# GR740_Memory.net
KiCad netlist of a schematic drawn in Altium Designer
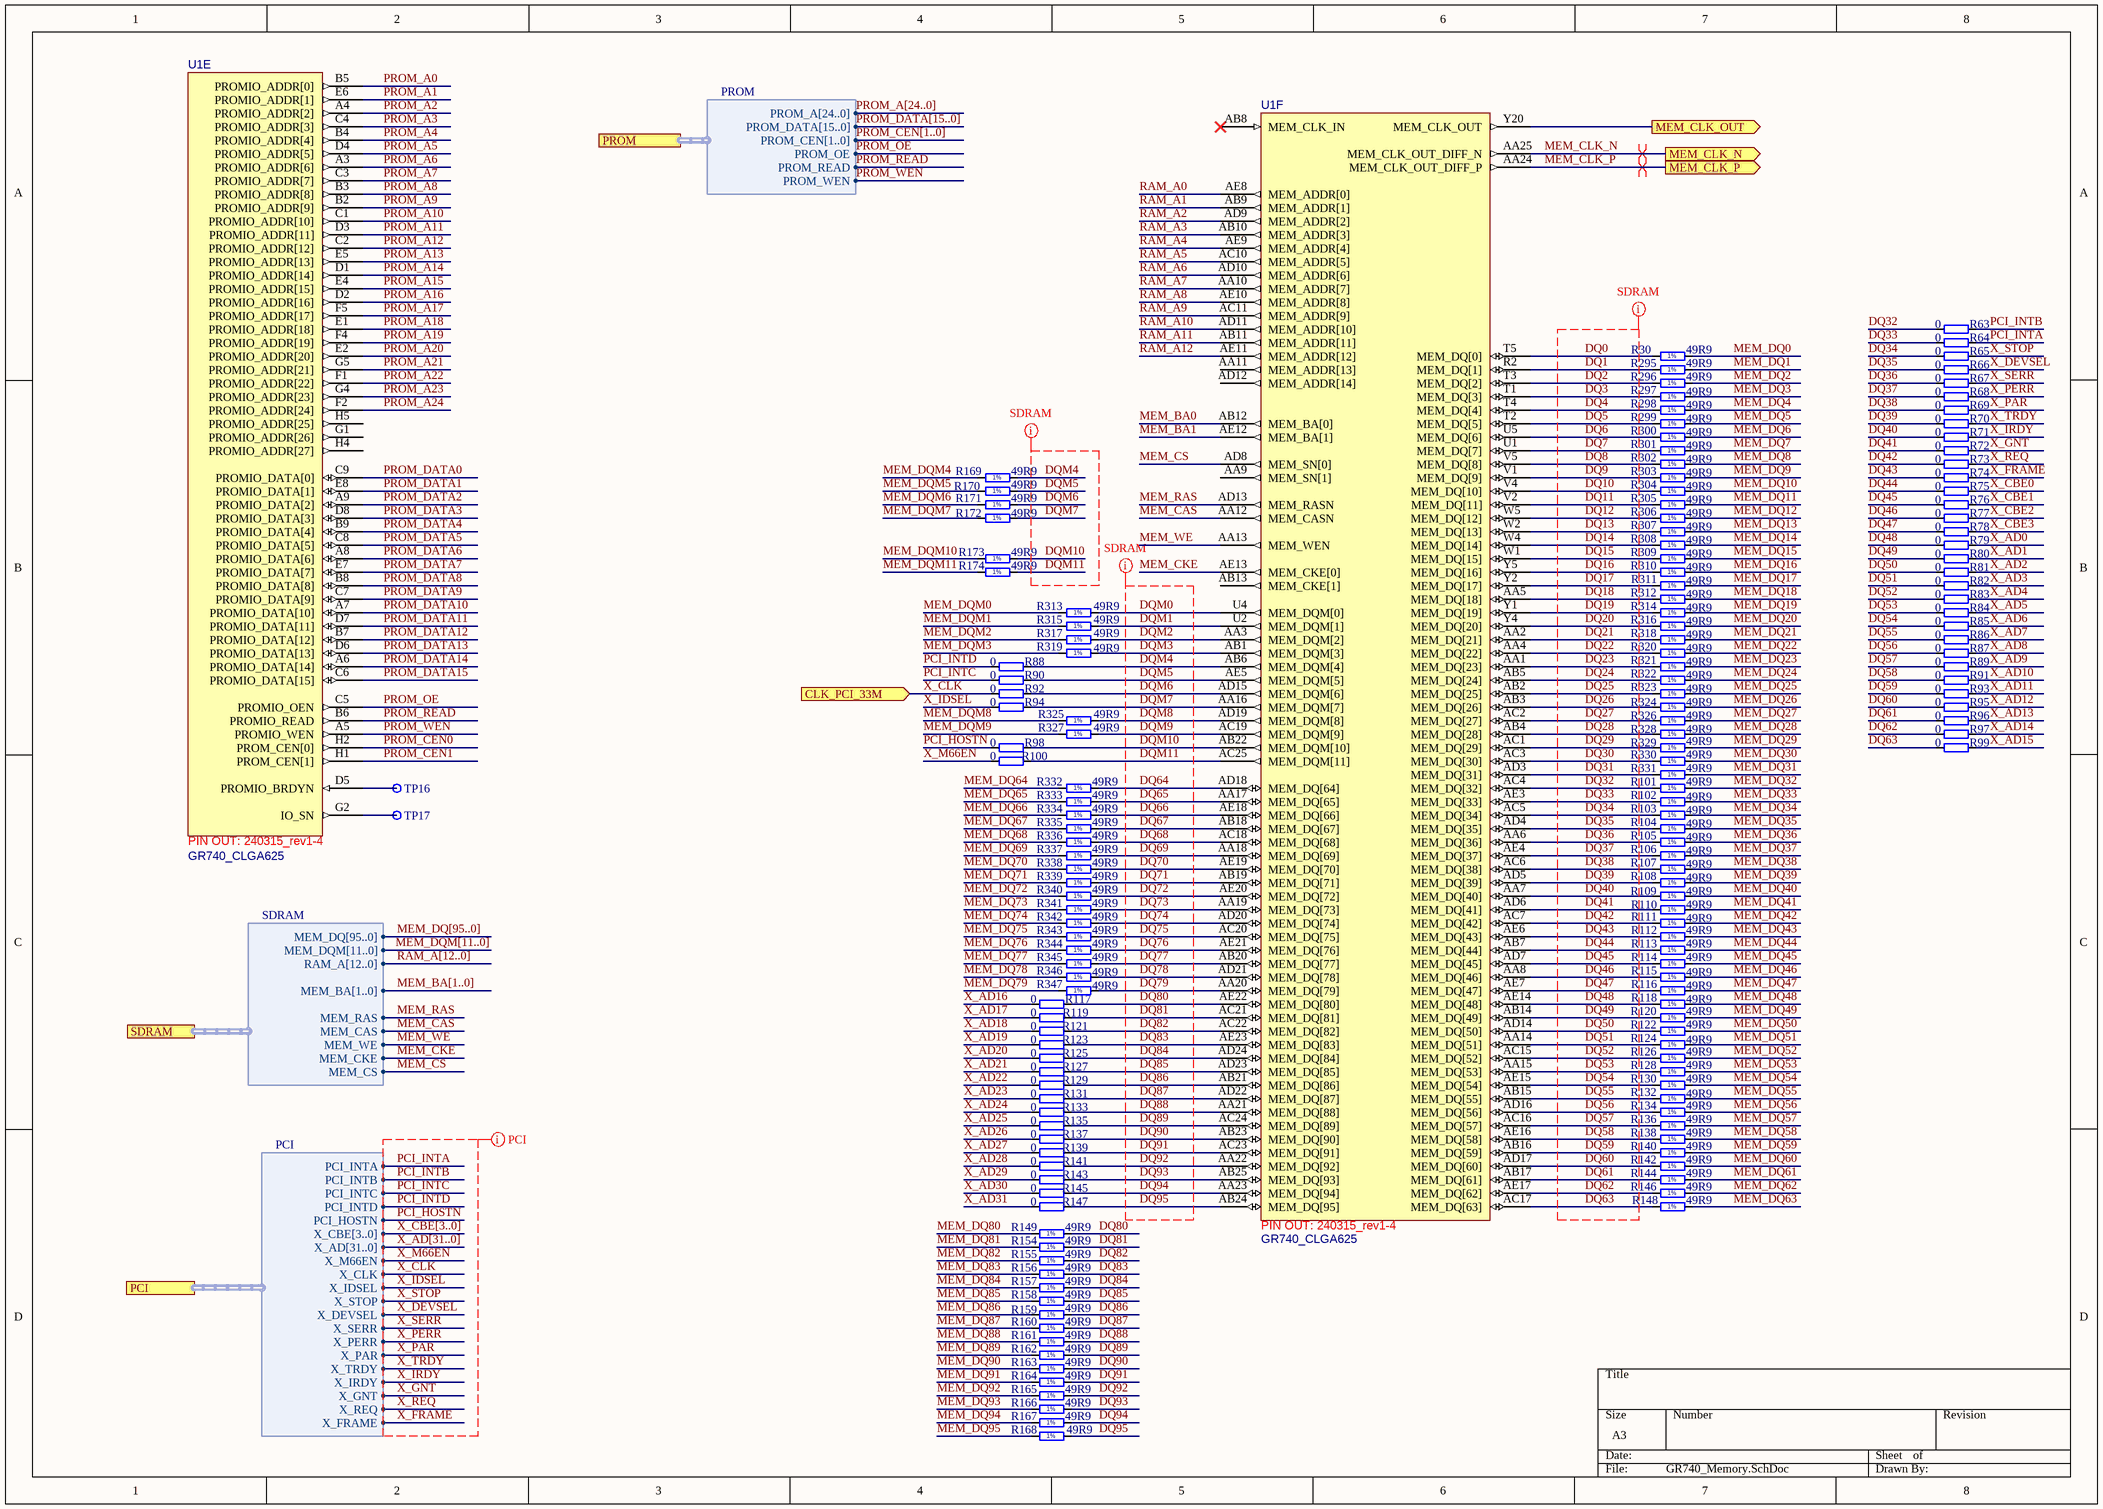
[diagram p0: GR740_Memory.SchDoc]

(export (version "E")
  (design (tool "Eeschema 10.0.6"))
  (components
    (comp (ref "R30")
      (value "49R9")
      (footprint "RESC0603X28N")
      (description "Resistor - 1%")
      (fields
        (field (name "PART NUMBER") "R0201_49R9_1%_0.05W_200PPM")
        (field (name "MANUFACTURER") "GENERIC")
        (field (name "AUTHOR") "CERN DEM BC")
      )
      (libsource (lib "Resistors") (part "Resistor - 1%"))
    )
    (comp (ref "R63")
      (value "0")
      (footprint "RESC0603X28N")
      (description "Resistor")
      (fields
        (field (name "PART NUMBER") "R0201_0R_JUMPER")
        (field (name "MANUFACTURER") "GENERIC")
        (field (name "AUTHOR") "CERN DEM JLC")
      )
      (libsource (lib "Resistors") (part "Resistor"))
    )
    (comp (ref "R64")
      (value "0")
      (footprint "RESC0603X28N")
      (description "Resistor")
      (fields
        (field (name "PART NUMBER") "R0201_0R_JUMPER")
        (field (name "MANUFACTURER") "GENERIC")
        (field (name "AUTHOR") "CERN DEM JLC")
      )
      (libsource (lib "Resistors") (part "Resistor"))
    )
    (comp (ref "R65")
      (value "0")
      (footprint "RESC0603X28N")
      (description "Resistor")
      (fields
        (field (name "PART NUMBER") "R0201_0R_JUMPER")
        (field (name "MANUFACTURER") "GENERIC")
        (field (name "AUTHOR") "CERN DEM JLC")
      )
      (libsource (lib "Resistors") (part "Resistor"))
    )
    (comp (ref "R66")
      (value "0")
      (footprint "RESC0603X28N")
      (description "Resistor")
      (fields
        (field (name "PART NUMBER") "R0201_0R_JUMPER")
        (field (name "MANUFACTURER") "GENERIC")
        (field (name "AUTHOR") "CERN DEM JLC")
      )
      (libsource (lib "Resistors") (part "Resistor"))
    )
    (comp (ref "R67")
      (value "0")
      (footprint "RESC0603X28N")
      (description "Resistor")
      (fields
        (field (name "PART NUMBER") "R0201_0R_JUMPER")
        (field (name "MANUFACTURER") "GENERIC")
        (field (name "AUTHOR") "CERN DEM JLC")
      )
      (libsource (lib "Resistors") (part "Resistor"))
    )
    (comp (ref "R68")
      (value "0")
      (footprint "RESC0603X28N")
      (description "Resistor")
      (fields
        (field (name "PART NUMBER") "R0201_0R_JUMPER")
        (field (name "MANUFACTURER") "GENERIC")
        (field (name "AUTHOR") "CERN DEM JLC")
      )
      (libsource (lib "Resistors") (part "Resistor"))
    )
    (comp (ref "R69")
      (value "0")
      (footprint "RESC0603X28N")
      (description "Resistor")
      (fields
        (field (name "PART NUMBER") "R0201_0R_JUMPER")
        (field (name "MANUFACTURER") "GENERIC")
        (field (name "AUTHOR") "CERN DEM JLC")
      )
      (libsource (lib "Resistors") (part "Resistor"))
    )
    (comp (ref "R70")
      (value "0")
      (footprint "RESC0603X28N")
      (description "Resistor")
      (fields
        (field (name "PART NUMBER") "R0201_0R_JUMPER")
        (field (name "MANUFACTURER") "GENERIC")
        (field (name "AUTHOR") "CERN DEM JLC")
      )
      (libsource (lib "Resistors") (part "Resistor"))
    )
    (comp (ref "R71")
      (value "0")
      (footprint "RESC0603X28N")
      (description "Resistor")
      (fields
        (field (name "PART NUMBER") "R0201_0R_JUMPER")
        (field (name "MANUFACTURER") "GENERIC")
        (field (name "AUTHOR") "CERN DEM JLC")
      )
      (libsource (lib "Resistors") (part "Resistor"))
    )
    (comp (ref "R72")
      (value "0")
      (footprint "RESC0603X28N")
      (description "Resistor")
      (fields
        (field (name "PART NUMBER") "R0201_0R_JUMPER")
        (field (name "MANUFACTURER") "GENERIC")
        (field (name "AUTHOR") "CERN DEM JLC")
      )
      (libsource (lib "Resistors") (part "Resistor"))
    )
    (comp (ref "R73")
      (value "0")
      (footprint "RESC0603X28N")
      (description "Resistor")
      (fields
        (field (name "PART NUMBER") "R0201_0R_JUMPER")
        (field (name "MANUFACTURER") "GENERIC")
        (field (name "AUTHOR") "CERN DEM JLC")
      )
      (libsource (lib "Resistors") (part "Resistor"))
    )
    (comp (ref "R74")
      (value "0")
      (footprint "RESC0603X28N")
      (description "Resistor")
      (fields
        (field (name "PART NUMBER") "R0201_0R_JUMPER")
        (field (name "MANUFACTURER") "GENERIC")
        (field (name "AUTHOR") "CERN DEM JLC")
      )
      (libsource (lib "Resistors") (part "Resistor"))
    )
    (comp (ref "R75")
      (value "0")
      (footprint "RESC0603X28N")
      (description "Resistor")
      (fields
        (field (name "PART NUMBER") "R0201_0R_JUMPER")
        (field (name "MANUFACTURER") "GENERIC")
        (field (name "AUTHOR") "CERN DEM JLC")
      )
      (libsource (lib "Resistors") (part "Resistor"))
    )
    (comp (ref "R76")
      (value "0")
      (footprint "RESC0603X28N")
      (description "Resistor")
      (fields
        (field (name "PART NUMBER") "R0201_0R_JUMPER")
        (field (name "MANUFACTURER") "GENERIC")
        (field (name "AUTHOR") "CERN DEM JLC")
      )
      (libsource (lib "Resistors") (part "Resistor"))
    )
    (comp (ref "R77")
      (value "0")
      (footprint "RESC0603X28N")
      (description "Resistor")
      (fields
        (field (name "PART NUMBER") "R0201_0R_JUMPER")
        (field (name "MANUFACTURER") "GENERIC")
        (field (name "AUTHOR") "CERN DEM JLC")
      )
      (libsource (lib "Resistors") (part "Resistor"))
    )
    (comp (ref "R78")
      (value "0")
      (footprint "RESC0603X28N")
      (description "Resistor")
      (fields
        (field (name "PART NUMBER") "R0201_0R_JUMPER")
        (field (name "MANUFACTURER") "GENERIC")
        (field (name "AUTHOR") "CERN DEM JLC")
      )
      (libsource (lib "Resistors") (part "Resistor"))
    )
    (comp (ref "R79")
      (value "0")
      (footprint "RESC0603X28N")
      (description "Resistor")
      (fields
        (field (name "PART NUMBER") "R0201_0R_JUMPER")
        (field (name "MANUFACTURER") "GENERIC")
        (field (name "AUTHOR") "CERN DEM JLC")
      )
      (libsource (lib "Resistors") (part "Resistor"))
    )
    (comp (ref "R80")
      (value "0")
      (footprint "RESC0603X28N")
      (description "Resistor")
      (fields
        (field (name "PART NUMBER") "R0201_0R_JUMPER")
        (field (name "MANUFACTURER") "GENERIC")
        (field (name "AUTHOR") "CERN DEM JLC")
      )
      (libsource (lib "Resistors") (part "Resistor"))
    )
    (comp (ref "R81")
      (value "0")
      (footprint "RESC0603X28N")
      (description "Resistor")
      (fields
        (field (name "PART NUMBER") "R0201_0R_JUMPER")
        (field (name "MANUFACTURER") "GENERIC")
        (field (name "AUTHOR") "CERN DEM JLC")
      )
      (libsource (lib "Resistors") (part "Resistor"))
    )
    (comp (ref "R82")
      (value "0")
      (footprint "RESC0603X28N")
      (description "Resistor")
      (fields
        (field (name "PART NUMBER") "R0201_0R_JUMPER")
        (field (name "MANUFACTURER") "GENERIC")
        (field (name "AUTHOR") "CERN DEM JLC")
      )
      (libsource (lib "Resistors") (part "Resistor"))
    )
    (comp (ref "R83")
      (value "0")
      (footprint "RESC0603X28N")
      (description "Resistor")
      (fields
        (field (name "PART NUMBER") "R0201_0R_JUMPER")
        (field (name "MANUFACTURER") "GENERIC")
        (field (name "AUTHOR") "CERN DEM JLC")
      )
      (libsource (lib "Resistors") (part "Resistor"))
    )
    (comp (ref "R84")
      (value "0")
      (footprint "RESC0603X28N")
      (description "Resistor")
      (fields
        (field (name "PART NUMBER") "R0201_0R_JUMPER")
        (field (name "MANUFACTURER") "GENERIC")
        (field (name "AUTHOR") "CERN DEM JLC")
      )
      (libsource (lib "Resistors") (part "Resistor"))
    )
    (comp (ref "R85")
      (value "0")
      (footprint "RESC0603X28N")
      (description "Resistor")
      (fields
        (field (name "PART NUMBER") "R0201_0R_JUMPER")
        (field (name "MANUFACTURER") "GENERIC")
        (field (name "AUTHOR") "CERN DEM JLC")
      )
      (libsource (lib "Resistors") (part "Resistor"))
    )
    (comp (ref "R86")
      (value "0")
      (footprint "RESC0603X28N")
      (description "Resistor")
      (fields
        (field (name "PART NUMBER") "R0201_0R_JUMPER")
        (field (name "MANUFACTURER") "GENERIC")
        (field (name "AUTHOR") "CERN DEM JLC")
      )
      (libsource (lib "Resistors") (part "Resistor"))
    )
    (comp (ref "R87")
      (value "0")
      (footprint "RESC0603X28N")
      (description "Resistor")
      (fields
        (field (name "PART NUMBER") "R0201_0R_JUMPER")
        (field (name "MANUFACTURER") "GENERIC")
        (field (name "AUTHOR") "CERN DEM JLC")
      )
      (libsource (lib "Resistors") (part "Resistor"))
    )
    (comp (ref "R88")
      (value "0")
      (footprint "RESC0603X28N")
      (description "Resistor")
      (fields
        (field (name "PART NUMBER") "R0201_0R_JUMPER")
        (field (name "MANUFACTURER") "GENERIC")
        (field (name "AUTHOR") "CERN DEM JLC")
      )
      (libsource (lib "Resistors") (part "Resistor"))
    )
    (comp (ref "R89")
      (value "0")
      (footprint "RESC0603X28N")
      (description "Resistor")
      (fields
        (field (name "PART NUMBER") "R0201_0R_JUMPER")
        (field (name "MANUFACTURER") "GENERIC")
        (field (name "AUTHOR") "CERN DEM JLC")
      )
      (libsource (lib "Resistors") (part "Resistor"))
    )
    (comp (ref "R90")
      (value "0")
      (footprint "RESC0603X28N")
      (description "Resistor")
      (fields
        (field (name "PART NUMBER") "R0201_0R_JUMPER")
        (field (name "MANUFACTURER") "GENERIC")
        (field (name "AUTHOR") "CERN DEM JLC")
      )
      (libsource (lib "Resistors") (part "Resistor"))
    )
    (comp (ref "R91")
      (value "0")
      (footprint "RESC0603X28N")
      (description "Resistor")
      (fields
        (field (name "PART NUMBER") "R0201_0R_JUMPER")
        (field (name "MANUFACTURER") "GENERIC")
        (field (name "AUTHOR") "CERN DEM JLC")
      )
      (libsource (lib "Resistors") (part "Resistor"))
    )
    (comp (ref "R92")
      (value "0")
      (footprint "RESC0603X28N")
      (description "Resistor")
      (fields
        (field (name "PART NUMBER") "R0201_0R_JUMPER")
        (field (name "MANUFACTURER") "GENERIC")
        (field (name "AUTHOR") "CERN DEM JLC")
      )
      (libsource (lib "Resistors") (part "Resistor"))
    )
    (comp (ref "R93")
      (value "0")
      (footprint "RESC0603X28N")
      (description "Resistor")
      (fields
        (field (name "PART NUMBER") "R0201_0R_JUMPER")
        (field (name "MANUFACTURER") "GENERIC")
        (field (name "AUTHOR") "CERN DEM JLC")
      )
      (libsource (lib "Resistors") (part "Resistor"))
    )
    (comp (ref "R94")
      (value "0")
      (footprint "RESC0603X28N")
      (description "Resistor")
      (fields
        (field (name "PART NUMBER") "R0201_0R_JUMPER")
        (field (name "MANUFACTURER") "GENERIC")
        (field (name "AUTHOR") "CERN DEM JLC")
      )
      (libsource (lib "Resistors") (part "Resistor"))
    )
    (comp (ref "R95")
      (value "0")
      (footprint "RESC0603X28N")
      (description "Resistor")
      (fields
        (field (name "PART NUMBER") "R0201_0R_JUMPER")
        (field (name "MANUFACTURER") "GENERIC")
        (field (name "AUTHOR") "CERN DEM JLC")
      )
      (libsource (lib "Resistors") (part "Resistor"))
    )
    (comp (ref "R96")
      (value "0")
      (footprint "RESC0603X28N")
      (description "Resistor")
      (fields
        (field (name "PART NUMBER") "R0201_0R_JUMPER")
        (field (name "MANUFACTURER") "GENERIC")
        (field (name "AUTHOR") "CERN DEM JLC")
      )
      (libsource (lib "Resistors") (part "Resistor"))
    )
    (comp (ref "R97")
      (value "0")
      (footprint "RESC0603X28N")
      (description "Resistor")
      (fields
        (field (name "PART NUMBER") "R0201_0R_JUMPER")
        (field (name "MANUFACTURER") "GENERIC")
        (field (name "AUTHOR") "CERN DEM JLC")
      )
      (libsource (lib "Resistors") (part "Resistor"))
    )
    (comp (ref "R98")
      (value "0")
      (footprint "RESC0603X28N")
      (description "Resistor")
      (fields
        (field (name "PART NUMBER") "R0201_0R_JUMPER")
        (field (name "MANUFACTURER") "GENERIC")
        (field (name "AUTHOR") "CERN DEM JLC")
      )
      (libsource (lib "Resistors") (part "Resistor"))
    )
    (comp (ref "R99")
      (value "0")
      (footprint "RESC0603X28N")
      (description "Resistor")
      (fields
        (field (name "PART NUMBER") "R0201_0R_JUMPER")
        (field (name "MANUFACTURER") "GENERIC")
        (field (name "AUTHOR") "CERN DEM JLC")
      )
      (libsource (lib "Resistors") (part "Resistor"))
    )
    (comp (ref "R100")
      (value "0")
      (footprint "RESC0603X28N")
      (description "Resistor")
      (fields
        (field (name "PART NUMBER") "R0201_0R_JUMPER")
        (field (name "MANUFACTURER") "GENERIC")
        (field (name "AUTHOR") "CERN DEM JLC")
      )
      (libsource (lib "Resistors") (part "Resistor"))
    )
    (comp (ref "R101")
      (value "49R9")
      (footprint "RESC0603X28N")
      (description "Resistor - 1%")
      (fields
        (field (name "PART NUMBER") "R0201_49R9_1%_0.05W_200PPM")
        (field (name "MANUFACTURER") "GENERIC")
        (field (name "AUTHOR") "CERN DEM BC")
      )
      (libsource (lib "Resistors") (part "Resistor - 1%"))
    )
    (comp (ref "R102")
      (value "49R9")
      (footprint "RESC0603X28N")
      (description "Resistor - 1%")
      (fields
        (field (name "PART NUMBER") "R0201_49R9_1%_0.05W_200PPM")
        (field (name "MANUFACTURER") "GENERIC")
        (field (name "AUTHOR") "CERN DEM BC")
      )
      (libsource (lib "Resistors") (part "Resistor - 1%"))
    )
    (comp (ref "R103")
      (value "49R9")
      (footprint "RESC0603X28N")
      (description "Resistor - 1%")
      (fields
        (field (name "PART NUMBER") "R0201_49R9_1%_0.05W_200PPM")
        (field (name "MANUFACTURER") "GENERIC")
        (field (name "AUTHOR") "CERN DEM BC")
      )
      (libsource (lib "Resistors") (part "Resistor - 1%"))
    )
    (comp (ref "R104")
      (value "49R9")
      (footprint "RESC0603X28N")
      (description "Resistor - 1%")
      (fields
        (field (name "PART NUMBER") "R0201_49R9_1%_0.05W_200PPM")
        (field (name "MANUFACTURER") "GENERIC")
        (field (name "AUTHOR") "CERN DEM BC")
      )
      (libsource (lib "Resistors") (part "Resistor - 1%"))
    )
    (comp (ref "R105")
      (value "49R9")
      (footprint "RESC0603X28N")
      (description "Resistor - 1%")
      (fields
        (field (name "PART NUMBER") "R0201_49R9_1%_0.05W_200PPM")
        (field (name "MANUFACTURER") "GENERIC")
        (field (name "AUTHOR") "CERN DEM BC")
      )
      (libsource (lib "Resistors") (part "Resistor - 1%"))
    )
    (comp (ref "R106")
      (value "49R9")
      (footprint "RESC0603X28N")
      (description "Resistor - 1%")
      (fields
        (field (name "PART NUMBER") "R0201_49R9_1%_0.05W_200PPM")
        (field (name "MANUFACTURER") "GENERIC")
        (field (name "AUTHOR") "CERN DEM BC")
      )
      (libsource (lib "Resistors") (part "Resistor - 1%"))
    )
    (comp (ref "R107")
      (value "49R9")
      (footprint "RESC0603X28N")
      (description "Resistor - 1%")
      (fields
        (field (name "PART NUMBER") "R0201_49R9_1%_0.05W_200PPM")
        (field (name "MANUFACTURER") "GENERIC")
        (field (name "AUTHOR") "CERN DEM BC")
      )
      (libsource (lib "Resistors") (part "Resistor - 1%"))
    )
    (comp (ref "R108")
      (value "49R9")
      (footprint "RESC0603X28N")
      (description "Resistor - 1%")
      (fields
        (field (name "PART NUMBER") "R0201_49R9_1%_0.05W_200PPM")
        (field (name "MANUFACTURER") "GENERIC")
        (field (name "AUTHOR") "CERN DEM BC")
      )
      (libsource (lib "Resistors") (part "Resistor - 1%"))
    )
    (comp (ref "R109")
      (value "49R9")
      (footprint "RESC0603X28N")
      (description "Resistor - 1%")
      (fields
        (field (name "PART NUMBER") "R0201_49R9_1%_0.05W_200PPM")
        (field (name "MANUFACTURER") "GENERIC")
        (field (name "AUTHOR") "CERN DEM BC")
      )
      (libsource (lib "Resistors") (part "Resistor - 1%"))
    )
    (comp (ref "R110")
      (value "49R9")
      (footprint "RESC0603X28N")
      (description "Resistor - 1%")
      (fields
        (field (name "PART NUMBER") "R0201_49R9_1%_0.05W_200PPM")
        (field (name "MANUFACTURER") "GENERIC")
        (field (name "AUTHOR") "CERN DEM BC")
      )
      (libsource (lib "Resistors") (part "Resistor - 1%"))
    )
    (comp (ref "R111")
      (value "49R9")
      (footprint "RESC0603X28N")
      (description "Resistor - 1%")
      (fields
        (field (name "PART NUMBER") "R0201_49R9_1%_0.05W_200PPM")
        (field (name "MANUFACTURER") "GENERIC")
        (field (name "AUTHOR") "CERN DEM BC")
      )
      (libsource (lib "Resistors") (part "Resistor - 1%"))
    )
    (comp (ref "R112")
      (value "49R9")
      (footprint "RESC0603X28N")
      (description "Resistor - 1%")
      (fields
        (field (name "PART NUMBER") "R0201_49R9_1%_0.05W_200PPM")
        (field (name "MANUFACTURER") "GENERIC")
        (field (name "AUTHOR") "CERN DEM BC")
      )
      (libsource (lib "Resistors") (part "Resistor - 1%"))
    )
    (comp (ref "R113")
      (value "49R9")
      (footprint "RESC0603X28N")
      (description "Resistor - 1%")
      (fields
        (field (name "PART NUMBER") "R0201_49R9_1%_0.05W_200PPM")
        (field (name "MANUFACTURER") "GENERIC")
        (field (name "AUTHOR") "CERN DEM BC")
      )
      (libsource (lib "Resistors") (part "Resistor - 1%"))
    )
    (comp (ref "R114")
      (value "49R9")
      (footprint "RESC0603X28N")
      (description "Resistor - 1%")
      (fields
        (field (name "PART NUMBER") "R0201_49R9_1%_0.05W_200PPM")
        (field (name "MANUFACTURER") "GENERIC")
        (field (name "AUTHOR") "CERN DEM BC")
      )
      (libsource (lib "Resistors") (part "Resistor - 1%"))
    )
    (comp (ref "R115")
      (value "49R9")
      (footprint "RESC0603X28N")
      (description "Resistor - 1%")
      (fields
        (field (name "PART NUMBER") "R0201_49R9_1%_0.05W_200PPM")
        (field (name "MANUFACTURER") "GENERIC")
        (field (name "AUTHOR") "CERN DEM BC")
      )
      (libsource (lib "Resistors") (part "Resistor - 1%"))
    )
    (comp (ref "R116")
      (value "49R9")
      (footprint "RESC0603X28N")
      (description "Resistor - 1%")
      (fields
        (field (name "PART NUMBER") "R0201_49R9_1%_0.05W_200PPM")
        (field (name "MANUFACTURER") "GENERIC")
        (field (name "AUTHOR") "CERN DEM BC")
      )
      (libsource (lib "Resistors") (part "Resistor - 1%"))
    )
    (comp (ref "R117")
      (value "0")
      (footprint "RESC0603X28N")
      (description "Resistor")
      (fields
        (field (name "PART NUMBER") "R0201_0R_JUMPER")
        (field (name "MANUFACTURER") "GENERIC")
        (field (name "AUTHOR") "CERN DEM JLC")
      )
      (libsource (lib "Resistors") (part "Resistor"))
    )
    (comp (ref "R118")
      (value "49R9")
      (footprint "RESC0603X28N")
      (description "Resistor - 1%")
      (fields
        (field (name "PART NUMBER") "R0201_49R9_1%_0.05W_200PPM")
        (field (name "MANUFACTURER") "GENERIC")
        (field (name "AUTHOR") "CERN DEM BC")
      )
      (libsource (lib "Resistors") (part "Resistor - 1%"))
    )
    (comp (ref "R119")
      (value "0")
      (footprint "RESC0603X28N")
      (description "Resistor")
      (fields
        (field (name "PART NUMBER") "R0201_0R_JUMPER")
        (field (name "MANUFACTURER") "GENERIC")
        (field (name "AUTHOR") "CERN DEM JLC")
      )
      (libsource (lib "Resistors") (part "Resistor"))
    )
    (comp (ref "R120")
      (value "49R9")
      (footprint "RESC0603X28N")
      (description "Resistor - 1%")
      (fields
        (field (name "PART NUMBER") "R0201_49R9_1%_0.05W_200PPM")
        (field (name "MANUFACTURER") "GENERIC")
        (field (name "AUTHOR") "CERN DEM BC")
      )
      (libsource (lib "Resistors") (part "Resistor - 1%"))
    )
    (comp (ref "R121")
      (value "0")
      (footprint "RESC0603X28N")
      (description "Resistor")
      (fields
        (field (name "PART NUMBER") "R0201_0R_JUMPER")
        (field (name "MANUFACTURER") "GENERIC")
        (field (name "AUTHOR") "CERN DEM JLC")
      )
      (libsource (lib "Resistors") (part "Resistor"))
    )
    (comp (ref "R122")
      (value "49R9")
      (footprint "RESC0603X28N")
      (description "Resistor - 1%")
      (fields
        (field (name "PART NUMBER") "R0201_49R9_1%_0.05W_200PPM")
        (field (name "MANUFACTURER") "GENERIC")
        (field (name "AUTHOR") "CERN DEM BC")
      )
      (libsource (lib "Resistors") (part "Resistor - 1%"))
    )
    (comp (ref "R123")
      (value "0")
      (footprint "RESC0603X28N")
      (description "Resistor")
      (fields
        (field (name "PART NUMBER") "R0201_0R_JUMPER")
        (field (name "MANUFACTURER") "GENERIC")
        (field (name "AUTHOR") "CERN DEM JLC")
      )
      (libsource (lib "Resistors") (part "Resistor"))
    )
    (comp (ref "R124")
      (value "49R9")
      (footprint "RESC0603X28N")
      (description "Resistor - 1%")
      (fields
        (field (name "PART NUMBER") "R0201_49R9_1%_0.05W_200PPM")
        (field (name "MANUFACTURER") "GENERIC")
        (field (name "AUTHOR") "CERN DEM BC")
      )
      (libsource (lib "Resistors") (part "Resistor - 1%"))
    )
    (comp (ref "R125")
      (value "0")
      (footprint "RESC0603X28N")
      (description "Resistor")
      (fields
        (field (name "PART NUMBER") "R0201_0R_JUMPER")
        (field (name "MANUFACTURER") "GENERIC")
        (field (name "AUTHOR") "CERN DEM JLC")
      )
      (libsource (lib "Resistors") (part "Resistor"))
    )
    (comp (ref "R126")
      (value "49R9")
      (footprint "RESC0603X28N")
      (description "Resistor - 1%")
      (fields
        (field (name "PART NUMBER") "R0201_49R9_1%_0.05W_200PPM")
        (field (name "MANUFACTURER") "GENERIC")
        (field (name "AUTHOR") "CERN DEM BC")
      )
      (libsource (lib "Resistors") (part "Resistor - 1%"))
    )
    (comp (ref "R127")
      (value "0")
      (footprint "RESC0603X28N")
      (description "Resistor")
      (fields
        (field (name "PART NUMBER") "R0201_0R_JUMPER")
        (field (name "MANUFACTURER") "GENERIC")
        (field (name "AUTHOR") "CERN DEM JLC")
      )
      (libsource (lib "Resistors") (part "Resistor"))
    )
    (comp (ref "R128")
      (value "49R9")
      (footprint "RESC0603X28N")
      (description "Resistor - 1%")
      (fields
        (field (name "PART NUMBER") "R0201_49R9_1%_0.05W_200PPM")
        (field (name "MANUFACTURER") "GENERIC")
        (field (name "AUTHOR") "CERN DEM BC")
      )
      (libsource (lib "Resistors") (part "Resistor - 1%"))
    )
    (comp (ref "R129")
      (value "0")
      (footprint "RESC0603X28N")
      (description "Resistor")
      (fields
        (field (name "PART NUMBER") "R0201_0R_JUMPER")
        (field (name "MANUFACTURER") "GENERIC")
        (field (name "AUTHOR") "CERN DEM JLC")
      )
      (libsource (lib "Resistors") (part "Resistor"))
    )
    (comp (ref "R130")
      (value "49R9")
      (footprint "RESC0603X28N")
      (description "Resistor - 1%")
      (fields
        (field (name "PART NUMBER") "R0201_49R9_1%_0.05W_200PPM")
        (field (name "MANUFACTURER") "GENERIC")
        (field (name "AUTHOR") "CERN DEM BC")
      )
      (libsource (lib "Resistors") (part "Resistor - 1%"))
    )
    (comp (ref "R131")
      (value "0")
      (footprint "RESC0603X28N")
      (description "Resistor")
      (fields
        (field (name "PART NUMBER") "R0201_0R_JUMPER")
        (field (name "MANUFACTURER") "GENERIC")
        (field (name "AUTHOR") "CERN DEM JLC")
      )
      (libsource (lib "Resistors") (part "Resistor"))
    )
    (comp (ref "R132")
      (value "49R9")
      (footprint "RESC0603X28N")
      (description "Resistor - 1%")
      (fields
        (field (name "PART NUMBER") "R0201_49R9_1%_0.05W_200PPM")
        (field (name "MANUFACTURER") "GENERIC")
        (field (name "AUTHOR") "CERN DEM BC")
      )
      (libsource (lib "Resistors") (part "Resistor - 1%"))
    )
    (comp (ref "R133")
      (value "0")
      (footprint "RESC0603X28N")
      (description "Resistor")
      (fields
        (field (name "PART NUMBER") "R0201_0R_JUMPER")
        (field (name "MANUFACTURER") "GENERIC")
        (field (name "AUTHOR") "CERN DEM JLC")
      )
      (libsource (lib "Resistors") (part "Resistor"))
    )
    (comp (ref "R134")
      (value "49R9")
      (footprint "RESC0603X28N")
      (description "Resistor - 1%")
      (fields
        (field (name "PART NUMBER") "R0201_49R9_1%_0.05W_200PPM")
        (field (name "MANUFACTURER") "GENERIC")
        (field (name "AUTHOR") "CERN DEM BC")
      )
      (libsource (lib "Resistors") (part "Resistor - 1%"))
    )
    (comp (ref "R135")
      (value "0")
      (footprint "RESC0603X28N")
      (description "Resistor")
      (fields
        (field (name "PART NUMBER") "R0201_0R_JUMPER")
        (field (name "MANUFACTURER") "GENERIC")
        (field (name "AUTHOR") "CERN DEM JLC")
      )
      (libsource (lib "Resistors") (part "Resistor"))
    )
    (comp (ref "R136")
      (value "49R9")
      (footprint "RESC0603X28N")
      (description "Resistor - 1%")
      (fields
        (field (name "PART NUMBER") "R0201_49R9_1%_0.05W_200PPM")
        (field (name "MANUFACTURER") "GENERIC")
        (field (name "AUTHOR") "CERN DEM BC")
      )
      (libsource (lib "Resistors") (part "Resistor - 1%"))
    )
    (comp (ref "R137")
      (value "0")
      (footprint "RESC0603X28N")
      (description "Resistor")
      (fields
        (field (name "PART NUMBER") "R0201_0R_JUMPER")
        (field (name "MANUFACTURER") "GENERIC")
        (field (name "AUTHOR") "CERN DEM JLC")
      )
      (libsource (lib "Resistors") (part "Resistor"))
    )
    (comp (ref "R138")
      (value "49R9")
      (footprint "RESC0603X28N")
      (description "Resistor - 1%")
      (fields
        (field (name "PART NUMBER") "R0201_49R9_1%_0.05W_200PPM")
        (field (name "MANUFACTURER") "GENERIC")
        (field (name "AUTHOR") "CERN DEM BC")
      )
      (libsource (lib "Resistors") (part "Resistor - 1%"))
    )
    (comp (ref "R139")
      (value "0")
      (footprint "RESC0603X28N")
      (description "Resistor")
      (fields
        (field (name "PART NUMBER") "R0201_0R_JUMPER")
        (field (name "MANUFACTURER") "GENERIC")
        (field (name "AUTHOR") "CERN DEM JLC")
      )
      (libsource (lib "Resistors") (part "Resistor"))
    )
    (comp (ref "R140")
      (value "49R9")
      (footprint "RESC0603X28N")
      (description "Resistor - 1%")
      (fields
        (field (name "PART NUMBER") "R0201_49R9_1%_0.05W_200PPM")
        (field (name "MANUFACTURER") "GENERIC")
        (field (name "AUTHOR") "CERN DEM BC")
      )
      (libsource (lib "Resistors") (part "Resistor - 1%"))
    )
    (comp (ref "R141")
      (value "0")
      (footprint "RESC0603X28N")
      (description "Resistor")
      (fields
        (field (name "PART NUMBER") "R0201_0R_JUMPER")
        (field (name "MANUFACTURER") "GENERIC")
        (field (name "AUTHOR") "CERN DEM JLC")
      )
      (libsource (lib "Resistors") (part "Resistor"))
    )
    (comp (ref "R142")
      (value "49R9")
      (footprint "RESC0603X28N")
      (description "Resistor - 1%")
      (fields
        (field (name "PART NUMBER") "R0201_49R9_1%_0.05W_200PPM")
        (field (name "MANUFACTURER") "GENERIC")
        (field (name "AUTHOR") "CERN DEM BC")
      )
      (libsource (lib "Resistors") (part "Resistor - 1%"))
    )
    (comp (ref "R143")
      (value "0")
      (footprint "RESC0603X28N")
      (description "Resistor")
      (fields
        (field (name "PART NUMBER") "R0201_0R_JUMPER")
        (field (name "MANUFACTURER") "GENERIC")
        (field (name "AUTHOR") "CERN DEM JLC")
      )
      (libsource (lib "Resistors") (part "Resistor"))
    )
    (comp (ref "R144")
      (value "49R9")
      (footprint "RESC0603X28N")
      (description "Resistor - 1%")
      (fields
        (field (name "PART NUMBER") "R0201_49R9_1%_0.05W_200PPM")
        (field (name "MANUFACTURER") "GENERIC")
        (field (name "AUTHOR") "CERN DEM BC")
      )
      (libsource (lib "Resistors") (part "Resistor - 1%"))
    )
    (comp (ref "R145")
      (value "0")
      (footprint "RESC0603X28N")
      (description "Resistor")
      (fields
        (field (name "PART NUMBER") "R0201_0R_JUMPER")
        (field (name "MANUFACTURER") "GENERIC")
        (field (name "AUTHOR") "CERN DEM JLC")
      )
      (libsource (lib "Resistors") (part "Resistor"))
    )
    (comp (ref "R146")
      (value "49R9")
      (footprint "RESC0603X28N")
      (description "Resistor - 1%")
      (fields
        (field (name "PART NUMBER") "R0201_49R9_1%_0.05W_200PPM")
        (field (name "MANUFACTURER") "GENERIC")
        (field (name "AUTHOR") "CERN DEM BC")
      )
      (libsource (lib "Resistors") (part "Resistor - 1%"))
    )
    (comp (ref "R147")
      (value "0")
      (footprint "RESC0603X28N")
      (description "Resistor")
      (fields
        (field (name "PART NUMBER") "R0201_0R_JUMPER")
        (field (name "MANUFACTURER") "GENERIC")
        (field (name "AUTHOR") "CERN DEM JLC")
      )
      (libsource (lib "Resistors") (part "Resistor"))
    )
    (comp (ref "R148")
      (value "49R9")
      (footprint "RESC0603X28N")
      (description "Resistor - 1%")
      (fields
        (field (name "PART NUMBER") "R0201_49R9_1%_0.05W_200PPM")
        (field (name "MANUFACTURER") "GENERIC")
        (field (name "AUTHOR") "CERN DEM BC")
      )
      (libsource (lib "Resistors") (part "Resistor - 1%"))
    )
    (comp (ref "R149")
      (value "49R9")
      (footprint "RESC0603X28N")
      (description "Resistor - 1%")
      (fields
        (field (name "PART NUMBER") "R0201_49R9_1%_0.05W_200PPM")
        (field (name "MANUFACTURER") "GENERIC")
        (field (name "AUTHOR") "CERN DEM BC")
      )
      (libsource (lib "Resistors") (part "Resistor - 1%"))
    )
    (comp (ref "R154")
      (value "49R9")
      (footprint "RESC0603X28N")
      (description "Resistor - 1%")
      (fields
        (field (name "PART NUMBER") "R0201_49R9_1%_0.05W_200PPM")
        (field (name "MANUFACTURER") "GENERIC")
        (field (name "AUTHOR") "CERN DEM BC")
      )
      (libsource (lib "Resistors") (part "Resistor - 1%"))
    )
    (comp (ref "R155")
      (value "49R9")
      (footprint "RESC0603X28N")
      (description "Resistor - 1%")
      (fields
        (field (name "PART NUMBER") "R0201_49R9_1%_0.05W_200PPM")
        (field (name "MANUFACTURER") "GENERIC")
        (field (name "AUTHOR") "CERN DEM BC")
      )
      (libsource (lib "Resistors") (part "Resistor - 1%"))
    )
    (comp (ref "R156")
      (value "49R9")
      (footprint "RESC0603X28N")
      (description "Resistor - 1%")
      (fields
        (field (name "PART NUMBER") "R0201_49R9_1%_0.05W_200PPM")
        (field (name "MANUFACTURER") "GENERIC")
        (field (name "AUTHOR") "CERN DEM BC")
      )
      (libsource (lib "Resistors") (part "Resistor - 1%"))
    )
    (comp (ref "R157")
      (value "49R9")
      (footprint "RESC0603X28N")
      (description "Resistor - 1%")
      (fields
        (field (name "PART NUMBER") "R0201_49R9_1%_0.05W_200PPM")
        (field (name "MANUFACTURER") "GENERIC")
        (field (name "AUTHOR") "CERN DEM BC")
      )
      (libsource (lib "Resistors") (part "Resistor - 1%"))
    )
    (comp (ref "R158")
      (value "49R9")
      (footprint "RESC0603X28N")
      (description "Resistor - 1%")
      (fields
        (field (name "PART NUMBER") "R0201_49R9_1%_0.05W_200PPM")
        (field (name "MANUFACTURER") "GENERIC")
        (field (name "AUTHOR") "CERN DEM BC")
      )
      (libsource (lib "Resistors") (part "Resistor - 1%"))
    )
    (comp (ref "R159")
      (value "49R9")
      (footprint "RESC0603X28N")
      (description "Resistor - 1%")
      (fields
        (field (name "PART NUMBER") "R0201_49R9_1%_0.05W_200PPM")
        (field (name "MANUFACTURER") "GENERIC")
        (field (name "AUTHOR") "CERN DEM BC")
      )
      (libsource (lib "Resistors") (part "Resistor - 1%"))
    )
    (comp (ref "R160")
      (value "49R9")
      (footprint "RESC0603X28N")
      (description "Resistor - 1%")
      (fields
        (field (name "PART NUMBER") "R0201_49R9_1%_0.05W_200PPM")
        (field (name "MANUFACTURER") "GENERIC")
        (field (name "AUTHOR") "CERN DEM BC")
      )
      (libsource (lib "Resistors") (part "Resistor - 1%"))
    )
    (comp (ref "R161")
      (value "49R9")
      (footprint "RESC0603X28N")
      (description "Resistor - 1%")
      (fields
        (field (name "PART NUMBER") "R0201_49R9_1%_0.05W_200PPM")
        (field (name "MANUFACTURER") "GENERIC")
        (field (name "AUTHOR") "CERN DEM BC")
      )
      (libsource (lib "Resistors") (part "Resistor - 1%"))
    )
    (comp (ref "R162")
      (value "49R9")
      (footprint "RESC0603X28N")
      (description "Resistor - 1%")
      (fields
        (field (name "PART NUMBER") "R0201_49R9_1%_0.05W_200PPM")
        (field (name "MANUFACTURER") "GENERIC")
        (field (name "AUTHOR") "CERN DEM BC")
      )
      (libsource (lib "Resistors") (part "Resistor - 1%"))
    )
    (comp (ref "R163")
      (value "49R9")
      (footprint "RESC0603X28N")
      (description "Resistor - 1%")
      (fields
        (field (name "PART NUMBER") "R0201_49R9_1%_0.05W_200PPM")
        (field (name "MANUFACTURER") "GENERIC")
        (field (name "AUTHOR") "CERN DEM BC")
      )
      (libsource (lib "Resistors") (part "Resistor - 1%"))
    )
    (comp (ref "R164")
      (value "49R9")
      (footprint "RESC0603X28N")
      (description "Resistor - 1%")
      (fields
        (field (name "PART NUMBER") "R0201_49R9_1%_0.05W_200PPM")
        (field (name "MANUFACTURER") "GENERIC")
        (field (name "AUTHOR") "CERN DEM BC")
      )
      (libsource (lib "Resistors") (part "Resistor - 1%"))
    )
    (comp (ref "R165")
      (value "49R9")
      (footprint "RESC0603X28N")
      (description "Resistor - 1%")
      (fields
        (field (name "PART NUMBER") "R0201_49R9_1%_0.05W_200PPM")
        (field (name "MANUFACTURER") "GENERIC")
        (field (name "AUTHOR") "CERN DEM BC")
      )
      (libsource (lib "Resistors") (part "Resistor - 1%"))
    )
    (comp (ref "R166")
      (value "49R9")
      (footprint "RESC0603X28N")
      (description "Resistor - 1%")
      (fields
        (field (name "PART NUMBER") "R0201_49R9_1%_0.05W_200PPM")
        (field (name "MANUFACTURER") "GENERIC")
        (field (name "AUTHOR") "CERN DEM BC")
      )
      (libsource (lib "Resistors") (part "Resistor - 1%"))
    )
    (comp (ref "R167")
      (value "49R9")
      (footprint "RESC0603X28N")
      (description "Resistor - 1%")
      (fields
        (field (name "PART NUMBER") "R0201_49R9_1%_0.05W_200PPM")
        (field (name "MANUFACTURER") "GENERIC")
        (field (name "AUTHOR") "CERN DEM BC")
      )
      (libsource (lib "Resistors") (part "Resistor - 1%"))
    )
    (comp (ref "R168")
      (value "49R9")
      (footprint "RESC0603X28N")
      (description "Resistor - 1%")
      (fields
        (field (name "PART NUMBER") "R0201_49R9_1%_0.05W_200PPM")
        (field (name "MANUFACTURER") "GENERIC")
        (field (name "AUTHOR") "CERN DEM BC")
      )
      (libsource (lib "Resistors") (part "Resistor - 1%"))
    )
    (comp (ref "R169")
      (value "49R9")
      (footprint "RESC0603X28N")
      (description "Resistor - 1%")
      (fields
        (field (name "PART NUMBER") "R0201_49R9_1%_0.05W_200PPM")
        (field (name "MANUFACTURER") "GENERIC")
        (field (name "AUTHOR") "CERN DEM BC")
      )
      (libsource (lib "Resistors") (part "Resistor - 1%"))
    )
    (comp (ref "R170")
      (value "49R9")
      (footprint "RESC0603X28N")
      (description "Resistor - 1%")
      (fields
        (field (name "PART NUMBER") "R0201_49R9_1%_0.05W_200PPM")
        (field (name "MANUFACTURER") "GENERIC")
        (field (name "AUTHOR") "CERN DEM BC")
      )
      (libsource (lib "Resistors") (part "Resistor - 1%"))
    )
    (comp (ref "R171")
      (value "49R9")
      (footprint "RESC0603X28N")
      (description "Resistor - 1%")
      (fields
        (field (name "PART NUMBER") "R0201_49R9_1%_0.05W_200PPM")
        (field (name "MANUFACTURER") "GENERIC")
        (field (name "AUTHOR") "CERN DEM BC")
      )
      (libsource (lib "Resistors") (part "Resistor - 1%"))
    )
    (comp (ref "R172")
      (value "49R9")
      (footprint "RESC0603X28N")
      (description "Resistor - 1%")
      (fields
        (field (name "PART NUMBER") "R0201_49R9_1%_0.05W_200PPM")
        (field (name "MANUFACTURER") "GENERIC")
        (field (name "AUTHOR") "CERN DEM BC")
      )
      (libsource (lib "Resistors") (part "Resistor - 1%"))
    )
    (comp (ref "R173")
      (value "49R9")
      (footprint "RESC0603X28N")
      (description "Resistor - 1%")
      (fields
        (field (name "PART NUMBER") "R0201_49R9_1%_0.05W_200PPM")
        (field (name "MANUFACTURER") "GENERIC")
        (field (name "AUTHOR") "CERN DEM BC")
      )
      (libsource (lib "Resistors") (part "Resistor - 1%"))
    )
    (comp (ref "R174")
      (value "49R9")
      (footprint "RESC0603X28N")
      (description "Resistor - 1%")
      (fields
        (field (name "PART NUMBER") "R0201_49R9_1%_0.05W_200PPM")
        (field (name "MANUFACTURER") "GENERIC")
        (field (name "AUTHOR") "CERN DEM BC")
      )
      (libsource (lib "Resistors") (part "Resistor - 1%"))
    )
    (comp (ref "R295")
      (value "49R9")
      (footprint "RESC0603X28N")
      (description "Resistor - 1%")
      (fields
        (field (name "PART NUMBER") "R0201_49R9_1%_0.05W_200PPM")
        (field (name "MANUFACTURER") "GENERIC")
        (field (name "AUTHOR") "CERN DEM BC")
      )
      (libsource (lib "Resistors") (part "Resistor - 1%"))
    )
    (comp (ref "R296")
      (value "49R9")
      (footprint "RESC0603X28N")
      (description "Resistor - 1%")
      (fields
        (field (name "PART NUMBER") "R0201_49R9_1%_0.05W_200PPM")
        (field (name "MANUFACTURER") "GENERIC")
        (field (name "AUTHOR") "CERN DEM BC")
      )
      (libsource (lib "Resistors") (part "Resistor - 1%"))
    )
    (comp (ref "R297")
      (value "49R9")
      (footprint "RESC0603X28N")
      (description "Resistor - 1%")
      (fields
        (field (name "PART NUMBER") "R0201_49R9_1%_0.05W_200PPM")
        (field (name "MANUFACTURER") "GENERIC")
        (field (name "AUTHOR") "CERN DEM BC")
      )
      (libsource (lib "Resistors") (part "Resistor - 1%"))
    )
    (comp (ref "R298")
      (value "49R9")
      (footprint "RESC0603X28N")
      (description "Resistor - 1%")
      (fields
        (field (name "PART NUMBER") "R0201_49R9_1%_0.05W_200PPM")
        (field (name "MANUFACTURER") "GENERIC")
        (field (name "AUTHOR") "CERN DEM BC")
      )
      (libsource (lib "Resistors") (part "Resistor - 1%"))
    )
    (comp (ref "R299")
      (value "49R9")
      (footprint "RESC0603X28N")
      (description "Resistor - 1%")
      (fields
        (field (name "PART NUMBER") "R0201_49R9_1%_0.05W_200PPM")
        (field (name "MANUFACTURER") "GENERIC")
        (field (name "AUTHOR") "CERN DEM BC")
      )
      (libsource (lib "Resistors") (part "Resistor - 1%"))
    )
    (comp (ref "R300")
      (value "49R9")
      (footprint "RESC0603X28N")
      (description "Resistor - 1%")
      (fields
        (field (name "PART NUMBER") "R0201_49R9_1%_0.05W_200PPM")
        (field (name "MANUFACTURER") "GENERIC")
        (field (name "AUTHOR") "CERN DEM BC")
      )
      (libsource (lib "Resistors") (part "Resistor - 1%"))
    )
    (comp (ref "R301")
      (value "49R9")
      (footprint "RESC0603X28N")
      (description "Resistor - 1%")
      (fields
        (field (name "PART NUMBER") "R0201_49R9_1%_0.05W_200PPM")
        (field (name "MANUFACTURER") "GENERIC")
        (field (name "AUTHOR") "CERN DEM BC")
      )
      (libsource (lib "Resistors") (part "Resistor - 1%"))
    )
    (comp (ref "R302")
      (value "49R9")
      (footprint "RESC0603X28N")
      (description "Resistor - 1%")
      (fields
        (field (name "PART NUMBER") "R0201_49R9_1%_0.05W_200PPM")
        (field (name "MANUFACTURER") "GENERIC")
        (field (name "AUTHOR") "CERN DEM BC")
      )
      (libsource (lib "Resistors") (part "Resistor - 1%"))
    )
    (comp (ref "R303")
      (value "49R9")
      (footprint "RESC0603X28N")
      (description "Resistor - 1%")
      (fields
        (field (name "PART NUMBER") "R0201_49R9_1%_0.05W_200PPM")
        (field (name "MANUFACTURER") "GENERIC")
        (field (name "AUTHOR") "CERN DEM BC")
      )
      (libsource (lib "Resistors") (part "Resistor - 1%"))
    )
    (comp (ref "R304")
      (value "49R9")
      (footprint "RESC0603X28N")
      (description "Resistor - 1%")
      (fields
        (field (name "PART NUMBER") "R0201_49R9_1%_0.05W_200PPM")
        (field (name "MANUFACTURER") "GENERIC")
        (field (name "AUTHOR") "CERN DEM BC")
      )
      (libsource (lib "Resistors") (part "Resistor - 1%"))
    )
    (comp (ref "R305")
      (value "49R9")
      (footprint "RESC0603X28N")
      (description "Resistor - 1%")
      (fields
        (field (name "PART NUMBER") "R0201_49R9_1%_0.05W_200PPM")
        (field (name "MANUFACTURER") "GENERIC")
        (field (name "AUTHOR") "CERN DEM BC")
      )
      (libsource (lib "Resistors") (part "Resistor - 1%"))
    )
    (comp (ref "R306")
      (value "49R9")
      (footprint "RESC0603X28N")
      (description "Resistor - 1%")
      (fields
        (field (name "PART NUMBER") "R0201_49R9_1%_0.05W_200PPM")
        (field (name "MANUFACTURER") "GENERIC")
        (field (name "AUTHOR") "CERN DEM BC")
      )
      (libsource (lib "Resistors") (part "Resistor - 1%"))
    )
    (comp (ref "R307")
      (value "49R9")
      (footprint "RESC0603X28N")
      (description "Resistor - 1%")
      (fields
        (field (name "PART NUMBER") "R0201_49R9_1%_0.05W_200PPM")
        (field (name "MANUFACTURER") "GENERIC")
        (field (name "AUTHOR") "CERN DEM BC")
      )
      (libsource (lib "Resistors") (part "Resistor - 1%"))
    )
    (comp (ref "R308")
      (value "49R9")
      (footprint "RESC0603X28N")
      (description "Resistor - 1%")
      (fields
        (field (name "PART NUMBER") "R0201_49R9_1%_0.05W_200PPM")
        (field (name "MANUFACTURER") "GENERIC")
        (field (name "AUTHOR") "CERN DEM BC")
      )
      (libsource (lib "Resistors") (part "Resistor - 1%"))
    )
    (comp (ref "R309")
      (value "49R9")
      (footprint "RESC0603X28N")
      (description "Resistor - 1%")
      (fields
        (field (name "PART NUMBER") "R0201_49R9_1%_0.05W_200PPM")
        (field (name "MANUFACTURER") "GENERIC")
        (field (name "AUTHOR") "CERN DEM BC")
      )
      (libsource (lib "Resistors") (part "Resistor - 1%"))
    )
    (comp (ref "R310")
      (value "49R9")
      (footprint "RESC0603X28N")
      (description "Resistor - 1%")
      (fields
        (field (name "PART NUMBER") "R0201_49R9_1%_0.05W_200PPM")
        (field (name "MANUFACTURER") "GENERIC")
        (field (name "AUTHOR") "CERN DEM BC")
      )
      (libsource (lib "Resistors") (part "Resistor - 1%"))
    )
    (comp (ref "R311")
      (value "49R9")
      (footprint "RESC0603X28N")
      (description "Resistor - 1%")
      (fields
        (field (name "PART NUMBER") "R0201_49R9_1%_0.05W_200PPM")
        (field (name "MANUFACTURER") "GENERIC")
        (field (name "AUTHOR") "CERN DEM BC")
      )
      (libsource (lib "Resistors") (part "Resistor - 1%"))
    )
    (comp (ref "R312")
      (value "49R9")
      (footprint "RESC0603X28N")
      (description "Resistor - 1%")
      (fields
        (field (name "PART NUMBER") "R0201_49R9_1%_0.05W_200PPM")
        (field (name "MANUFACTURER") "GENERIC")
        (field (name "AUTHOR") "CERN DEM BC")
      )
      (libsource (lib "Resistors") (part "Resistor - 1%"))
    )
    (comp (ref "R313")
      (value "49R9")
      (footprint "RESC0603X28N")
      (description "Resistor - 1%")
      (fields
        (field (name "PART NUMBER") "R0201_49R9_1%_0.05W_200PPM")
        (field (name "MANUFACTURER") "GENERIC")
        (field (name "AUTHOR") "CERN DEM BC")
      )
      (libsource (lib "Resistors") (part "Resistor - 1%"))
    )
    (comp (ref "R314")
      (value "49R9")
      (footprint "RESC0603X28N")
      (description "Resistor - 1%")
      (fields
        (field (name "PART NUMBER") "R0201_49R9_1%_0.05W_200PPM")
        (field (name "MANUFACTURER") "GENERIC")
        (field (name "AUTHOR") "CERN DEM BC")
      )
      (libsource (lib "Resistors") (part "Resistor - 1%"))
    )
    (comp (ref "R315")
      (value "49R9")
      (footprint "RESC0603X28N")
      (description "Resistor - 1%")
      (fields
        (field (name "PART NUMBER") "R0201_49R9_1%_0.05W_200PPM")
        (field (name "MANUFACTURER") "GENERIC")
        (field (name "AUTHOR") "CERN DEM BC")
      )
      (libsource (lib "Resistors") (part "Resistor - 1%"))
    )
    (comp (ref "R316")
      (value "49R9")
      (footprint "RESC0603X28N")
      (description "Resistor - 1%")
      (fields
        (field (name "PART NUMBER") "R0201_49R9_1%_0.05W_200PPM")
        (field (name "MANUFACTURER") "GENERIC")
        (field (name "AUTHOR") "CERN DEM BC")
      )
      (libsource (lib "Resistors") (part "Resistor - 1%"))
    )
    (comp (ref "R317")
      (value "49R9")
      (footprint "RESC0603X28N")
      (description "Resistor - 1%")
      (fields
        (field (name "PART NUMBER") "R0201_49R9_1%_0.05W_200PPM")
        (field (name "MANUFACTURER") "GENERIC")
        (field (name "AUTHOR") "CERN DEM BC")
      )
      (libsource (lib "Resistors") (part "Resistor - 1%"))
    )
    (comp (ref "R318")
      (value "49R9")
      (footprint "RESC0603X28N")
      (description "Resistor - 1%")
      (fields
        (field (name "PART NUMBER") "R0201_49R9_1%_0.05W_200PPM")
        (field (name "MANUFACTURER") "GENERIC")
        (field (name "AUTHOR") "CERN DEM BC")
      )
      (libsource (lib "Resistors") (part "Resistor - 1%"))
    )
    (comp (ref "R319")
      (value "49R9")
      (footprint "RESC0603X28N")
      (description "Resistor - 1%")
      (fields
        (field (name "PART NUMBER") "R0201_49R9_1%_0.05W_200PPM")
        (field (name "MANUFACTURER") "GENERIC")
        (field (name "AUTHOR") "CERN DEM BC")
      )
      (libsource (lib "Resistors") (part "Resistor - 1%"))
    )
    (comp (ref "R320")
      (value "49R9")
      (footprint "RESC0603X28N")
      (description "Resistor - 1%")
      (fields
        (field (name "PART NUMBER") "R0201_49R9_1%_0.05W_200PPM")
        (field (name "MANUFACTURER") "GENERIC")
        (field (name "AUTHOR") "CERN DEM BC")
      )
      (libsource (lib "Resistors") (part "Resistor - 1%"))
    )
    (comp (ref "R321")
      (value "49R9")
      (footprint "RESC0603X28N")
      (description "Resistor - 1%")
      (fields
        (field (name "PART NUMBER") "R0201_49R9_1%_0.05W_200PPM")
        (field (name "MANUFACTURER") "GENERIC")
        (field (name "AUTHOR") "CERN DEM BC")
      )
      (libsource (lib "Resistors") (part "Resistor - 1%"))
    )
    (comp (ref "R322")
      (value "49R9")
      (footprint "RESC0603X28N")
      (description "Resistor - 1%")
      (fields
        (field (name "PART NUMBER") "R0201_49R9_1%_0.05W_200PPM")
        (field (name "MANUFACTURER") "GENERIC")
        (field (name "AUTHOR") "CERN DEM BC")
      )
      (libsource (lib "Resistors") (part "Resistor - 1%"))
    )
    (comp (ref "R323")
      (value "49R9")
      (footprint "RESC0603X28N")
      (description "Resistor - 1%")
      (fields
        (field (name "PART NUMBER") "R0201_49R9_1%_0.05W_200PPM")
        (field (name "MANUFACTURER") "GENERIC")
        (field (name "AUTHOR") "CERN DEM BC")
      )
      (libsource (lib "Resistors") (part "Resistor - 1%"))
    )
    (comp (ref "R324")
      (value "49R9")
      (footprint "RESC0603X28N")
      (description "Resistor - 1%")
      (fields
        (field (name "PART NUMBER") "R0201_49R9_1%_0.05W_200PPM")
        (field (name "MANUFACTURER") "GENERIC")
        (field (name "AUTHOR") "CERN DEM BC")
      )
      (libsource (lib "Resistors") (part "Resistor - 1%"))
    )
    (comp (ref "R325")
      (value "49R9")
      (footprint "RESC0603X28N")
      (description "Resistor - 1%")
      (fields
        (field (name "PART NUMBER") "R0201_49R9_1%_0.05W_200PPM")
        (field (name "MANUFACTURER") "GENERIC")
        (field (name "AUTHOR") "CERN DEM BC")
      )
      (libsource (lib "Resistors") (part "Resistor - 1%"))
    )
    (comp (ref "R326")
      (value "49R9")
      (footprint "RESC0603X28N")
      (description "Resistor - 1%")
      (fields
        (field (name "PART NUMBER") "R0201_49R9_1%_0.05W_200PPM")
        (field (name "MANUFACTURER") "GENERIC")
        (field (name "AUTHOR") "CERN DEM BC")
      )
      (libsource (lib "Resistors") (part "Resistor - 1%"))
    )
    (comp (ref "R327")
      (value "49R9")
      (footprint "RESC0603X28N")
      (description "Resistor - 1%")
      (fields
        (field (name "PART NUMBER") "R0201_49R9_1%_0.05W_200PPM")
        (field (name "MANUFACTURER") "GENERIC")
        (field (name "AUTHOR") "CERN DEM BC")
      )
      (libsource (lib "Resistors") (part "Resistor - 1%"))
    )
    (comp (ref "R328")
      (value "49R9")
      (footprint "RESC0603X28N")
      (description "Resistor - 1%")
      (fields
        (field (name "PART NUMBER") "R0201_49R9_1%_0.05W_200PPM")
        (field (name "MANUFACTURER") "GENERIC")
        (field (name "AUTHOR") "CERN DEM BC")
      )
      (libsource (lib "Resistors") (part "Resistor - 1%"))
    )
    (comp (ref "R329")
      (value "49R9")
      (footprint "RESC0603X28N")
      (description "Resistor - 1%")
      (fields
        (field (name "PART NUMBER") "R0201_49R9_1%_0.05W_200PPM")
        (field (name "MANUFACTURER") "GENERIC")
        (field (name "AUTHOR") "CERN DEM BC")
      )
      (libsource (lib "Resistors") (part "Resistor - 1%"))
    )
    (comp (ref "R330")
      (value "49R9")
      (footprint "RESC0603X28N")
      (description "Resistor - 1%")
      (fields
        (field (name "PART NUMBER") "R0201_49R9_1%_0.05W_200PPM")
        (field (name "MANUFACTURER") "GENERIC")
        (field (name "AUTHOR") "CERN DEM BC")
      )
      (libsource (lib "Resistors") (part "Resistor - 1%"))
    )
    (comp (ref "R331")
      (value "49R9")
      (footprint "RESC0603X28N")
      (description "Resistor - 1%")
      (fields
        (field (name "PART NUMBER") "R0201_49R9_1%_0.05W_200PPM")
        (field (name "MANUFACTURER") "GENERIC")
        (field (name "AUTHOR") "CERN DEM BC")
      )
      (libsource (lib "Resistors") (part "Resistor - 1%"))
    )
    (comp (ref "R332")
      (value "49R9")
      (footprint "RESC0603X28N")
      (description "Resistor - 1%")
      (fields
        (field (name "PART NUMBER") "R0201_49R9_1%_0.05W_200PPM")
        (field (name "MANUFACTURER") "GENERIC")
        (field (name "AUTHOR") "CERN DEM BC")
      )
      (libsource (lib "Resistors") (part "Resistor - 1%"))
    )
    (comp (ref "R333")
      (value "49R9")
      (footprint "RESC0603X28N")
      (description "Resistor - 1%")
      (fields
        (field (name "PART NUMBER") "R0201_49R9_1%_0.05W_200PPM")
        (field (name "MANUFACTURER") "GENERIC")
        (field (name "AUTHOR") "CERN DEM BC")
      )
      (libsource (lib "Resistors") (part "Resistor - 1%"))
    )
    (comp (ref "R334")
      (value "49R9")
      (footprint "RESC0603X28N")
      (description "Resistor - 1%")
      (fields
        (field (name "PART NUMBER") "R0201_49R9_1%_0.05W_200PPM")
        (field (name "MANUFACTURER") "GENERIC")
        (field (name "AUTHOR") "CERN DEM BC")
      )
      (libsource (lib "Resistors") (part "Resistor - 1%"))
    )
    (comp (ref "R335")
      (value "49R9")
      (footprint "RESC0603X28N")
      (description "Resistor - 1%")
      (fields
        (field (name "PART NUMBER") "R0201_49R9_1%_0.05W_200PPM")
        (field (name "MANUFACTURER") "GENERIC")
        (field (name "AUTHOR") "CERN DEM BC")
      )
      (libsource (lib "Resistors") (part "Resistor - 1%"))
    )
    (comp (ref "R336")
      (value "49R9")
      (footprint "RESC0603X28N")
      (description "Resistor - 1%")
      (fields
        (field (name "PART NUMBER") "R0201_49R9_1%_0.05W_200PPM")
        (field (name "MANUFACTURER") "GENERIC")
        (field (name "AUTHOR") "CERN DEM BC")
      )
      (libsource (lib "Resistors") (part "Resistor - 1%"))
    )
    (comp (ref "R337")
      (value "49R9")
      (footprint "RESC0603X28N")
      (description "Resistor - 1%")
      (fields
        (field (name "PART NUMBER") "R0201_49R9_1%_0.05W_200PPM")
        (field (name "MANUFACTURER") "GENERIC")
        (field (name "AUTHOR") "CERN DEM BC")
      )
      (libsource (lib "Resistors") (part "Resistor - 1%"))
    )
    (comp (ref "R338")
      (value "49R9")
      (footprint "RESC0603X28N")
      (description "Resistor - 1%")
      (fields
        (field (name "PART NUMBER") "R0201_49R9_1%_0.05W_200PPM")
        (field (name "MANUFACTURER") "GENERIC")
        (field (name "AUTHOR") "CERN DEM BC")
      )
      (libsource (lib "Resistors") (part "Resistor - 1%"))
    )
    (comp (ref "R339")
      (value "49R9")
      (footprint "RESC0603X28N")
      (description "Resistor - 1%")
      (fields
        (field (name "PART NUMBER") "R0201_49R9_1%_0.05W_200PPM")
        (field (name "MANUFACTURER") "GENERIC")
        (field (name "AUTHOR") "CERN DEM BC")
      )
      (libsource (lib "Resistors") (part "Resistor - 1%"))
    )
    (comp (ref "R340")
      (value "49R9")
      (footprint "RESC0603X28N")
      (description "Resistor - 1%")
      (fields
        (field (name "PART NUMBER") "R0201_49R9_1%_0.05W_200PPM")
        (field (name "MANUFACTURER") "GENERIC")
        (field (name "AUTHOR") "CERN DEM BC")
      )
      (libsource (lib "Resistors") (part "Resistor - 1%"))
    )
    (comp (ref "R341")
      (value "49R9")
      (footprint "RESC0603X28N")
      (description "Resistor - 1%")
      (fields
        (field (name "PART NUMBER") "R0201_49R9_1%_0.05W_200PPM")
        (field (name "MANUFACTURER") "GENERIC")
        (field (name "AUTHOR") "CERN DEM BC")
      )
      (libsource (lib "Resistors") (part "Resistor - 1%"))
    )
    (comp (ref "R342")
      (value "49R9")
      (footprint "RESC0603X28N")
      (description "Resistor - 1%")
      (fields
        (field (name "PART NUMBER") "R0201_49R9_1%_0.05W_200PPM")
        (field (name "MANUFACTURER") "GENERIC")
        (field (name "AUTHOR") "CERN DEM BC")
      )
      (libsource (lib "Resistors") (part "Resistor - 1%"))
    )
    (comp (ref "R343")
      (value "49R9")
      (footprint "RESC0603X28N")
      (description "Resistor - 1%")
      (fields
        (field (name "PART NUMBER") "R0201_49R9_1%_0.05W_200PPM")
        (field (name "MANUFACTURER") "GENERIC")
        (field (name "AUTHOR") "CERN DEM BC")
      )
      (libsource (lib "Resistors") (part "Resistor - 1%"))
    )
    (comp (ref "R344")
      (value "49R9")
      (footprint "RESC0603X28N")
      (description "Resistor - 1%")
      (fields
        (field (name "PART NUMBER") "R0201_49R9_1%_0.05W_200PPM")
        (field (name "MANUFACTURER") "GENERIC")
        (field (name "AUTHOR") "CERN DEM BC")
      )
      (libsource (lib "Resistors") (part "Resistor - 1%"))
    )
    (comp (ref "R345")
      (value "49R9")
      (footprint "RESC0603X28N")
      (description "Resistor - 1%")
      (fields
        (field (name "PART NUMBER") "R0201_49R9_1%_0.05W_200PPM")
        (field (name "MANUFACTURER") "GENERIC")
        (field (name "AUTHOR") "CERN DEM BC")
      )
      (libsource (lib "Resistors") (part "Resistor - 1%"))
    )
    (comp (ref "R346")
      (value "49R9")
      (footprint "RESC0603X28N")
      (description "Resistor - 1%")
      (fields
        (field (name "PART NUMBER") "R0201_49R9_1%_0.05W_200PPM")
        (field (name "MANUFACTURER") "GENERIC")
        (field (name "AUTHOR") "CERN DEM BC")
      )
      (libsource (lib "Resistors") (part "Resistor - 1%"))
    )
    (comp (ref "R347")
      (value "49R9")
      (footprint "RESC0603X28N")
      (description "Resistor - 1%")
      (fields
        (field (name "PART NUMBER") "R0201_49R9_1%_0.05W_200PPM")
        (field (name "MANUFACTURER") "GENERIC")
        (field (name "AUTHOR") "CERN DEM BC")
      )
      (libsource (lib "Resistors") (part "Resistor - 1%"))
    )
    (comp (ref "TP16")
      (value "Test Point")
      (footprint "TPS127")
      (fields (field (name "PART NUMBER") "SMD_PAD_1.27X1.27MM") (field (name "AUTHOR") "CERN DEM JLC"))
      (libsource (lib "Eletro-mechanical") (part "Test Point"))
    )
    (comp (ref "TP17")
      (value "Test Point")
      (footprint "TPS127")
      (fields (field (name "PART NUMBER") "SMD_PAD_1.27X1.27MM") (field (name "AUTHOR") "CERN DEM JLC"))
      (libsource (lib "Eletro-mechanical") (part "Test Point"))
    )
    (comp (ref "U1")
      (value "GR740_CLGA625")
      (footprint "BGA625C100P25X25_3182X3182X1543")
      (libsource (lib "GR740_CLGA625") (part "GR740_CLGA625"))
    )
  )
  (nets
    (net (code "4") (name "/DQ0") (class "Default")
      (node (ref "R30") (pin "1") (pinfunction "1_1") (pintype "passive"))
      (node (ref "U1") (pin "T5") (pinfunction "MEM_DQ[0]_T5") (pintype "bidirectional"))
    )
    (net (code "5") (name "/DQ1") (class "Default")
      (node (ref "R295") (pin "1") (pinfunction "1_1") (pintype "passive"))
      (node (ref "U1") (pin "R2") (pinfunction "MEM_DQ[1]_R2") (pintype "bidirectional"))
    )
    (net (code "6") (name "/DQ2") (class "Default")
      (node (ref "R296") (pin "1") (pinfunction "1_1") (pintype "passive"))
      (node (ref "U1") (pin "T3") (pinfunction "MEM_DQ[2]_T3") (pintype "bidirectional"))
    )
    (net (code "7") (name "/DQ3") (class "Default")
      (node (ref "R297") (pin "1") (pinfunction "1_1") (pintype "passive"))
      (node (ref "U1") (pin "T1") (pinfunction "MEM_DQ[3]_T1") (pintype "bidirectional"))
    )
    (net (code "8") (name "/DQ4") (class "Default")
      (node (ref "R298") (pin "1") (pinfunction "1_1") (pintype "passive"))
      (node (ref "U1") (pin "T4") (pinfunction "MEM_DQ[4]_T4") (pintype "bidirectional"))
    )
    (net (code "9") (name "/DQ5") (class "Default")
      (node (ref "R299") (pin "1") (pinfunction "1_1") (pintype "passive"))
      (node (ref "U1") (pin "T2") (pinfunction "MEM_DQ[5]_T2") (pintype "bidirectional"))
    )
    (net (code "10") (name "/DQ6") (class "Default")
      (node (ref "R300") (pin "1") (pinfunction "1_1") (pintype "passive"))
      (node (ref "U1") (pin "U5") (pinfunction "MEM_DQ[6]_U5") (pintype "bidirectional"))
    )
    (net (code "11") (name "/DQ7") (class "Default")
      (node (ref "R301") (pin "1") (pinfunction "1_1") (pintype "passive"))
      (node (ref "U1") (pin "U1") (pinfunction "MEM_DQ[7]_U1") (pintype "bidirectional"))
    )
    (net (code "12") (name "/DQ8") (class "Default")
      (node (ref "R302") (pin "1") (pinfunction "1_1") (pintype "passive"))
      (node (ref "U1") (pin "V5") (pinfunction "MEM_DQ[8]_V5") (pintype "bidirectional"))
    )
    (net (code "13") (name "/DQ9") (class "Default")
      (node (ref "R303") (pin "1") (pinfunction "1_1") (pintype "passive"))
      (node (ref "U1") (pin "V1") (pinfunction "MEM_DQ[9]_V1") (pintype "bidirectional"))
    )
    (net (code "14") (name "/DQ10") (class "Default")
      (node (ref "R304") (pin "1") (pinfunction "1_1") (pintype "passive"))
      (node (ref "U1") (pin "V4") (pinfunction "MEM_DQ[10]_V4") (pintype "bidirectional"))
    )
    (net (code "15") (name "/DQ11") (class "Default")
      (node (ref "R305") (pin "1") (pinfunction "1_1") (pintype "passive"))
      (node (ref "U1") (pin "V2") (pinfunction "MEM_DQ[11]_V2") (pintype "bidirectional"))
    )
    (net (code "16") (name "/DQ12") (class "Default")
      (node (ref "R306") (pin "1") (pinfunction "1_1") (pintype "passive"))
      (node (ref "U1") (pin "W5") (pinfunction "MEM_DQ[12]_W5") (pintype "bidirectional"))
    )
    (net (code "17") (name "/DQ13") (class "Default")
      (node (ref "R307") (pin "1") (pinfunction "1_1") (pintype "passive"))
      (node (ref "U1") (pin "W2") (pinfunction "MEM_DQ[13]_W2") (pintype "bidirectional"))
    )
    (net (code "18") (name "/DQ14") (class "Default")
      (node (ref "R308") (pin "1") (pinfunction "1_1") (pintype "passive"))
      (node (ref "U1") (pin "W4") (pinfunction "MEM_DQ[14]_W4") (pintype "bidirectional"))
    )
    (net (code "19") (name "/DQ15") (class "Default")
      (node (ref "R309") (pin "1") (pinfunction "1_1") (pintype "passive"))
      (node (ref "U1") (pin "W1") (pinfunction "MEM_DQ[15]_W1") (pintype "bidirectional"))
    )
    (net (code "20") (name "/DQ16") (class "Default")
      (node (ref "R310") (pin "1") (pinfunction "1_1") (pintype "passive"))
      (node (ref "U1") (pin "Y5") (pinfunction "MEM_DQ[16]_Y5") (pintype "bidirectional"))
    )
    (net (code "21") (name "/DQ17") (class "Default")
      (node (ref "R311") (pin "1") (pinfunction "1_1") (pintype "passive"))
      (node (ref "U1") (pin "Y2") (pinfunction "MEM_DQ[17]_Y2") (pintype "bidirectional"))
    )
    (net (code "22") (name "/DQ18") (class "Default")
      (node (ref "R312") (pin "1") (pinfunction "1_1") (pintype "passive"))
      (node (ref "U1") (pin "AA5") (pinfunction "MEM_DQ[18]_AA5") (pintype "bidirectional"))
    )
    (net (code "23") (name "/DQ19") (class "Default")
      (node (ref "R314") (pin "1") (pinfunction "1_1") (pintype "passive"))
      (node (ref "U1") (pin "Y1") (pinfunction "MEM_DQ[19]_Y1") (pintype "bidirectional"))
    )
    (net (code "24") (name "/DQ20") (class "Default")
      (node (ref "R316") (pin "1") (pinfunction "1_1") (pintype "passive"))
      (node (ref "U1") (pin "Y4") (pinfunction "MEM_DQ[20]_Y4") (pintype "bidirectional"))
    )
    (net (code "25") (name "/DQ21") (class "Default")
      (node (ref "R318") (pin "1") (pinfunction "1_1") (pintype "passive"))
      (node (ref "U1") (pin "AA2") (pinfunction "MEM_DQ[21]_AA2") (pintype "bidirectional"))
    )
    (net (code "26") (name "/DQ22") (class "Default")
      (node (ref "R320") (pin "1") (pinfunction "1_1") (pintype "passive"))
      (node (ref "U1") (pin "AA4") (pinfunction "MEM_DQ[22]_AA4") (pintype "bidirectional"))
    )
    (net (code "27") (name "/DQ23") (class "Default")
      (node (ref "R321") (pin "1") (pinfunction "1_1") (pintype "passive"))
      (node (ref "U1") (pin "AA1") (pinfunction "MEM_DQ[23]_AA1") (pintype "bidirectional"))
    )
    (net (code "28") (name "/DQ24") (class "Default")
      (node (ref "R322") (pin "1") (pinfunction "1_1") (pintype "passive"))
      (node (ref "U1") (pin "AB5") (pinfunction "MEM_DQ[24]_AB5") (pintype "bidirectional"))
    )
    (net (code "29") (name "/DQ25") (class "Default")
      (node (ref "R323") (pin "1") (pinfunction "1_1") (pintype "passive"))
      (node (ref "U1") (pin "AB2") (pinfunction "MEM_DQ[25]_AB2") (pintype "bidirectional"))
    )
    (net (code "30") (name "/DQ26") (class "Default")
      (node (ref "R324") (pin "1") (pinfunction "1_1") (pintype "passive"))
      (node (ref "U1") (pin "AB3") (pinfunction "MEM_DQ[26]_AB3") (pintype "bidirectional"))
    )
    (net (code "31") (name "/DQ27") (class "Default")
      (node (ref "R326") (pin "1") (pinfunction "1_1") (pintype "passive"))
      (node (ref "U1") (pin "AC2") (pinfunction "MEM_DQ[27]_AC2") (pintype "bidirectional"))
    )
    (net (code "32") (name "/DQ28") (class "Default")
      (node (ref "R328") (pin "1") (pinfunction "1_1") (pintype "passive"))
      (node (ref "U1") (pin "AB4") (pinfunction "MEM_DQ[28]_AB4") (pintype "bidirectional"))
    )
    (net (code "33") (name "/DQ29") (class "Default")
      (node (ref "R329") (pin "1") (pinfunction "1_1") (pintype "passive"))
      (node (ref "U1") (pin "AC1") (pinfunction "MEM_DQ[29]_AC1") (pintype "bidirectional"))
    )
    (net (code "34") (name "/DQ30") (class "Default")
      (node (ref "R330") (pin "1") (pinfunction "1_1") (pintype "passive"))
      (node (ref "U1") (pin "AC3") (pinfunction "MEM_DQ[30]_AC3") (pintype "bidirectional"))
    )
    (net (code "35") (name "/DQ31") (class "Default")
      (node (ref "R331") (pin "1") (pinfunction "1_1") (pintype "passive"))
      (node (ref "U1") (pin "AD3") (pinfunction "MEM_DQ[31]_AD3") (pintype "bidirectional"))
    )
    (net (code "36") (name "/DQ32") (class "Default")
      (node (ref "R101") (pin "1") (pinfunction "1_1") (pintype "passive"))
      (node (ref "R63") (pin "1") (pinfunction "1_1") (pintype "passive"))
      (node (ref "U1") (pin "AC4") (pinfunction "MEM_DQ[32]_AC4") (pintype "bidirectional"))
    )
    (net (code "37") (name "/DQ33") (class "Default")
      (node (ref "R102") (pin "1") (pinfunction "1_1") (pintype "passive"))
      (node (ref "R64") (pin "1") (pinfunction "1_1") (pintype "passive"))
      (node (ref "U1") (pin "AE3") (pinfunction "MEM_DQ[33]_AE3") (pintype "bidirectional"))
    )
    (net (code "38") (name "/DQ34") (class "Default")
      (node (ref "R103") (pin "1") (pinfunction "1_1") (pintype "passive"))
      (node (ref "R65") (pin "1") (pinfunction "1_1") (pintype "passive"))
      (node (ref "U1") (pin "AC5") (pinfunction "MEM_DQ[34]_AC5") (pintype "bidirectional"))
    )
    (net (code "39") (name "/DQ35") (class "Default")
      (node (ref "R104") (pin "1") (pinfunction "1_1") (pintype "passive"))
      (node (ref "R66") (pin "1") (pinfunction "1_1") (pintype "passive"))
      (node (ref "U1") (pin "AD4") (pinfunction "MEM_DQ[35]_AD4") (pintype "bidirectional"))
    )
    (net (code "40") (name "/DQ36") (class "Default")
      (node (ref "R105") (pin "1") (pinfunction "1_1") (pintype "passive"))
      (node (ref "R67") (pin "1") (pinfunction "1_1") (pintype "passive"))
      (node (ref "U1") (pin "AA6") (pinfunction "MEM_DQ[36]_AA6") (pintype "bidirectional"))
    )
    (net (code "41") (name "/DQ37") (class "Default")
      (node (ref "R106") (pin "1") (pinfunction "1_1") (pintype "passive"))
      (node (ref "R68") (pin "1") (pinfunction "1_1") (pintype "passive"))
      (node (ref "U1") (pin "AE4") (pinfunction "MEM_DQ[37]_AE4") (pintype "bidirectional"))
    )
    (net (code "42") (name "/DQ38") (class "Default")
      (node (ref "R107") (pin "1") (pinfunction "1_1") (pintype "passive"))
      (node (ref "R69") (pin "1") (pinfunction "1_1") (pintype "passive"))
      (node (ref "U1") (pin "AC6") (pinfunction "MEM_DQ[38]_AC6") (pintype "bidirectional"))
    )
    (net (code "43") (name "/DQ39") (class "Default")
      (node (ref "R108") (pin "1") (pinfunction "1_1") (pintype "passive"))
      (node (ref "R70") (pin "1") (pinfunction "1_1") (pintype "passive"))
      (node (ref "U1") (pin "AD5") (pinfunction "MEM_DQ[39]_AD5") (pintype "bidirectional"))
    )
    (net (code "44") (name "/DQ40") (class "Default")
      (node (ref "R109") (pin "1") (pinfunction "1_1") (pintype "passive"))
      (node (ref "R71") (pin "1") (pinfunction "1_1") (pintype "passive"))
      (node (ref "U1") (pin "AA7") (pinfunction "MEM_DQ[40]_AA7") (pintype "bidirectional"))
    )
    (net (code "45") (name "/DQ41") (class "Default")
      (node (ref "R110") (pin "1") (pinfunction "1_1") (pintype "passive"))
      (node (ref "R72") (pin "1") (pinfunction "1_1") (pintype "passive"))
      (node (ref "U1") (pin "AD6") (pinfunction "MEM_DQ[41]_AD6") (pintype "bidirectional"))
    )
    (net (code "46") (name "/DQ42") (class "Default")
      (node (ref "R111") (pin "1") (pinfunction "1_1") (pintype "passive"))
      (node (ref "R73") (pin "1") (pinfunction "1_1") (pintype "passive"))
      (node (ref "U1") (pin "AC7") (pinfunction "MEM_DQ[42]_AC7") (pintype "bidirectional"))
    )
    (net (code "47") (name "/DQ43") (class "Default")
      (node (ref "R112") (pin "1") (pinfunction "1_1") (pintype "passive"))
      (node (ref "R74") (pin "1") (pinfunction "1_1") (pintype "passive"))
      (node (ref "U1") (pin "AE6") (pinfunction "MEM_DQ[43]_AE6") (pintype "bidirectional"))
    )
    (net (code "48") (name "/DQ44") (class "Default")
      (node (ref "R113") (pin "1") (pinfunction "1_1") (pintype "passive"))
      (node (ref "R75") (pin "1") (pinfunction "1_1") (pintype "passive"))
      (node (ref "U1") (pin "AB7") (pinfunction "MEM_DQ[44]_AB7") (pintype "bidirectional"))
    )
    (net (code "49") (name "/DQ45") (class "Default")
      (node (ref "R114") (pin "1") (pinfunction "1_1") (pintype "passive"))
      (node (ref "R76") (pin "1") (pinfunction "1_1") (pintype "passive"))
      (node (ref "U1") (pin "AD7") (pinfunction "MEM_DQ[45]_AD7") (pintype "bidirectional"))
    )
    (net (code "50") (name "/DQ46") (class "Default")
      (node (ref "R115") (pin "1") (pinfunction "1_1") (pintype "passive"))
      (node (ref "R77") (pin "1") (pinfunction "1_1") (pintype "passive"))
      (node (ref "U1") (pin "AA8") (pinfunction "MEM_DQ[46]_AA8") (pintype "bidirectional"))
    )
    (net (code "51") (name "/DQ47") (class "Default")
      (node (ref "R116") (pin "1") (pinfunction "1_1") (pintype "passive"))
      (node (ref "R78") (pin "1") (pinfunction "1_1") (pintype "passive"))
      (node (ref "U1") (pin "AE7") (pinfunction "MEM_DQ[47]_AE7") (pintype "bidirectional"))
    )
    (net (code "52") (name "/DQ48") (class "Default")
      (node (ref "R118") (pin "1") (pinfunction "1_1") (pintype "passive"))
      (node (ref "R79") (pin "1") (pinfunction "1_1") (pintype "passive"))
      (node (ref "U1") (pin "AE14") (pinfunction "MEM_DQ[48]_AE14") (pintype "bidirectional"))
    )
    (net (code "53") (name "/DQ49") (class "Default")
      (node (ref "R120") (pin "1") (pinfunction "1_1") (pintype "passive"))
      (node (ref "R80") (pin "1") (pinfunction "1_1") (pintype "passive"))
      (node (ref "U1") (pin "AB14") (pinfunction "MEM_DQ[49]_AB14") (pintype "bidirectional"))
    )
    (net (code "54") (name "/DQ50") (class "Default")
      (node (ref "R122") (pin "1") (pinfunction "1_1") (pintype "passive"))
      (node (ref "R81") (pin "1") (pinfunction "1_1") (pintype "passive"))
      (node (ref "U1") (pin "AD14") (pinfunction "MEM_DQ[50]_AD14") (pintype "bidirectional"))
    )
    (net (code "55") (name "/DQ51") (class "Default")
      (node (ref "R124") (pin "1") (pinfunction "1_1") (pintype "passive"))
      (node (ref "R82") (pin "1") (pinfunction "1_1") (pintype "passive"))
      (node (ref "U1") (pin "AA14") (pinfunction "MEM_DQ[51]_AA14") (pintype "bidirectional"))
    )
    (net (code "56") (name "/DQ52") (class "Default")
      (node (ref "R126") (pin "1") (pinfunction "1_1") (pintype "passive"))
      (node (ref "R83") (pin "1") (pinfunction "1_1") (pintype "passive"))
      (node (ref "U1") (pin "AC15") (pinfunction "MEM_DQ[52]_AC15") (pintype "bidirectional"))
    )
    (net (code "57") (name "/DQ53") (class "Default")
      (node (ref "R128") (pin "1") (pinfunction "1_1") (pintype "passive"))
      (node (ref "R84") (pin "1") (pinfunction "1_1") (pintype "passive"))
      (node (ref "U1") (pin "AA15") (pinfunction "MEM_DQ[53]_AA15") (pintype "bidirectional"))
    )
    (net (code "58") (name "/DQ54") (class "Default")
      (node (ref "R130") (pin "1") (pinfunction "1_1") (pintype "passive"))
      (node (ref "R85") (pin "1") (pinfunction "1_1") (pintype "passive"))
      (node (ref "U1") (pin "AE15") (pinfunction "MEM_DQ[54]_AE15") (pintype "bidirectional"))
    )
    (net (code "59") (name "/DQ55") (class "Default")
      (node (ref "R132") (pin "1") (pinfunction "1_1") (pintype "passive"))
      (node (ref "R86") (pin "1") (pinfunction "1_1") (pintype "passive"))
      (node (ref "U1") (pin "AB15") (pinfunction "MEM_DQ[55]_AB15") (pintype "bidirectional"))
    )
    (net (code "60") (name "/DQ56") (class "Default")
      (node (ref "R134") (pin "1") (pinfunction "1_1") (pintype "passive"))
      (node (ref "R87") (pin "1") (pinfunction "1_1") (pintype "passive"))
      (node (ref "U1") (pin "AD16") (pinfunction "MEM_DQ[56]_AD16") (pintype "bidirectional"))
    )
    (net (code "61") (name "/DQ57") (class "Default")
      (node (ref "R136") (pin "1") (pinfunction "1_1") (pintype "passive"))
      (node (ref "R89") (pin "1") (pinfunction "1_1") (pintype "passive"))
      (node (ref "U1") (pin "AC16") (pinfunction "MEM_DQ[57]_AC16") (pintype "bidirectional"))
    )
    (net (code "62") (name "/DQ58") (class "Default")
      (node (ref "R138") (pin "1") (pinfunction "1_1") (pintype "passive"))
      (node (ref "R91") (pin "1") (pinfunction "1_1") (pintype "passive"))
      (node (ref "U1") (pin "AE16") (pinfunction "MEM_DQ[58]_AE16") (pintype "bidirectional"))
    )
    (net (code "63") (name "/DQ59") (class "Default")
      (node (ref "R140") (pin "1") (pinfunction "1_1") (pintype "passive"))
      (node (ref "R93") (pin "1") (pinfunction "1_1") (pintype "passive"))
      (node (ref "U1") (pin "AB16") (pinfunction "MEM_DQ[59]_AB16") (pintype "bidirectional"))
    )
    (net (code "64") (name "/DQ60") (class "Default")
      (node (ref "R142") (pin "1") (pinfunction "1_1") (pintype "passive"))
      (node (ref "R95") (pin "1") (pinfunction "1_1") (pintype "passive"))
      (node (ref "U1") (pin "AD17") (pinfunction "MEM_DQ[60]_AD17") (pintype "bidirectional"))
    )
    (net (code "65") (name "/DQ61") (class "Default")
      (node (ref "R144") (pin "1") (pinfunction "1_1") (pintype "passive"))
      (node (ref "R96") (pin "1") (pinfunction "1_1") (pintype "passive"))
      (node (ref "U1") (pin "AB17") (pinfunction "MEM_DQ[61]_AB17") (pintype "bidirectional"))
    )
    (net (code "66") (name "/DQ62") (class "Default")
      (node (ref "R146") (pin "1") (pinfunction "1_1") (pintype "passive"))
      (node (ref "R97") (pin "1") (pinfunction "1_1") (pintype "passive"))
      (node (ref "U1") (pin "AE17") (pinfunction "MEM_DQ[62]_AE17") (pintype "bidirectional"))
    )
    (net (code "67") (name "/DQ63") (class "Default")
      (node (ref "R148") (pin "1") (pinfunction "1_1") (pintype "passive"))
      (node (ref "R99") (pin "1") (pinfunction "1_1") (pintype "passive"))
      (node (ref "U1") (pin "AC17") (pinfunction "MEM_DQ[63]_AC17") (pintype "bidirectional"))
    )
    (net (code "68") (name "/DQ64") (class "Default")
      (node (ref "R332") (pin "2") (pinfunction "2_2") (pintype "passive"))
      (node (ref "U1") (pin "AD18") (pinfunction "MEM_DQ[64]_AD18") (pintype "bidirectional"))
    )
    (net (code "69") (name "/DQ65") (class "Default")
      (node (ref "R333") (pin "2") (pinfunction "2_2") (pintype "passive"))
      (node (ref "U1") (pin "AA17") (pinfunction "MEM_DQ[65]_AA17") (pintype "bidirectional"))
    )
    (net (code "70") (name "/DQ66") (class "Default")
      (node (ref "R334") (pin "2") (pinfunction "2_2") (pintype "passive"))
      (node (ref "U1") (pin "AE18") (pinfunction "MEM_DQ[66]_AE18") (pintype "bidirectional"))
    )
    (net (code "71") (name "/DQ67") (class "Default")
      (node (ref "R335") (pin "2") (pinfunction "2_2") (pintype "passive"))
      (node (ref "U1") (pin "AB18") (pinfunction "MEM_DQ[67]_AB18") (pintype "bidirectional"))
    )
    (net (code "72") (name "/DQ68") (class "Default")
      (node (ref "R336") (pin "2") (pinfunction "2_2") (pintype "passive"))
      (node (ref "U1") (pin "AC18") (pinfunction "MEM_DQ[68]_AC18") (pintype "bidirectional"))
    )
    (net (code "73") (name "/DQ69") (class "Default")
      (node (ref "R337") (pin "2") (pinfunction "2_2") (pintype "passive"))
      (node (ref "U1") (pin "AA18") (pinfunction "MEM_DQ[69]_AA18") (pintype "bidirectional"))
    )
    (net (code "74") (name "/DQ70") (class "Default")
      (node (ref "R338") (pin "2") (pinfunction "2_2") (pintype "passive"))
      (node (ref "U1") (pin "AE19") (pinfunction "MEM_DQ[70]_AE19") (pintype "bidirectional"))
    )
    (net (code "75") (name "/DQ71") (class "Default")
      (node (ref "R339") (pin "2") (pinfunction "2_2") (pintype "passive"))
      (node (ref "U1") (pin "AB19") (pinfunction "MEM_DQ[71]_AB19") (pintype "bidirectional"))
    )
    (net (code "76") (name "/DQ72") (class "Default")
      (node (ref "R340") (pin "2") (pinfunction "2_2") (pintype "passive"))
      (node (ref "U1") (pin "AE20") (pinfunction "MEM_DQ[72]_AE20") (pintype "bidirectional"))
    )
    (net (code "77") (name "/DQ73") (class "Default")
      (node (ref "R341") (pin "2") (pinfunction "2_2") (pintype "passive"))
      (node (ref "U1") (pin "AA19") (pinfunction "MEM_DQ[73]_AA19") (pintype "bidirectional"))
    )
    (net (code "78") (name "/DQ74") (class "Default")
      (node (ref "R342") (pin "2") (pinfunction "2_2") (pintype "passive"))
      (node (ref "U1") (pin "AD20") (pinfunction "MEM_DQ[74]_AD20") (pintype "bidirectional"))
    )
    (net (code "79") (name "/DQ75") (class "Default")
      (node (ref "R343") (pin "2") (pinfunction "2_2") (pintype "passive"))
      (node (ref "U1") (pin "AC20") (pinfunction "MEM_DQ[75]_AC20") (pintype "bidirectional"))
    )
    (net (code "80") (name "/DQ76") (class "Default")
      (node (ref "R344") (pin "2") (pinfunction "2_2") (pintype "passive"))
      (node (ref "U1") (pin "AE21") (pinfunction "MEM_DQ[76]_AE21") (pintype "bidirectional"))
    )
    (net (code "81") (name "/DQ77") (class "Default")
      (node (ref "R345") (pin "2") (pinfunction "2_2") (pintype "passive"))
      (node (ref "U1") (pin "AB20") (pinfunction "MEM_DQ[77]_AB20") (pintype "bidirectional"))
    )
    (net (code "82") (name "/DQ78") (class "Default")
      (node (ref "R346") (pin "2") (pinfunction "2_2") (pintype "passive"))
      (node (ref "U1") (pin "AD21") (pinfunction "MEM_DQ[78]_AD21") (pintype "bidirectional"))
    )
    (net (code "83") (name "/DQ79") (class "Default")
      (node (ref "R347") (pin "2") (pinfunction "2_2") (pintype "passive"))
      (node (ref "U1") (pin "AA20") (pinfunction "MEM_DQ[79]_AA20") (pintype "bidirectional"))
    )
    (net (code "84") (name "/DQ80") (class "Default")
      (node (ref "R117") (pin "2") (pinfunction "2_2") (pintype "passive"))
      (node (ref "R149") (pin "2") (pinfunction "2_2") (pintype "passive"))
      (node (ref "U1") (pin "AE22") (pinfunction "MEM_DQ[80]_AE22") (pintype "bidirectional"))
    )
    (net (code "85") (name "/DQ81") (class "Default")
      (node (ref "R119") (pin "2") (pinfunction "2_2") (pintype "passive"))
      (node (ref "R154") (pin "2") (pinfunction "2_2") (pintype "passive"))
      (node (ref "U1") (pin "AC21") (pinfunction "MEM_DQ[81]_AC21") (pintype "bidirectional"))
    )
    (net (code "86") (name "/DQ82") (class "Default")
      (node (ref "R121") (pin "2") (pinfunction "2_2") (pintype "passive"))
      (node (ref "R155") (pin "2") (pinfunction "2_2") (pintype "passive"))
      (node (ref "U1") (pin "AC22") (pinfunction "MEM_DQ[82]_AC22") (pintype "bidirectional"))
    )
    (net (code "87") (name "/DQ83") (class "Default")
      (node (ref "R123") (pin "2") (pinfunction "2_2") (pintype "passive"))
      (node (ref "R156") (pin "2") (pinfunction "2_2") (pintype "passive"))
      (node (ref "U1") (pin "AE23") (pinfunction "MEM_DQ[83]_AE23") (pintype "bidirectional"))
    )
    (net (code "88") (name "/DQ84") (class "Default")
      (node (ref "R125") (pin "2") (pinfunction "2_2") (pintype "passive"))
      (node (ref "R157") (pin "2") (pinfunction "2_2") (pintype "passive"))
      (node (ref "U1") (pin "AD24") (pinfunction "MEM_DQ[84]_AD24") (pintype "bidirectional"))
    )
    (net (code "89") (name "/DQ85") (class "Default")
      (node (ref "R127") (pin "2") (pinfunction "2_2") (pintype "passive"))
      (node (ref "R158") (pin "2") (pinfunction "2_2") (pintype "passive"))
      (node (ref "U1") (pin "AD23") (pinfunction "MEM_DQ[85]_AD23") (pintype "bidirectional"))
    )
    (net (code "90") (name "/DQ86") (class "Default")
      (node (ref "R129") (pin "2") (pinfunction "2_2") (pintype "passive"))
      (node (ref "R159") (pin "2") (pinfunction "2_2") (pintype "passive"))
      (node (ref "U1") (pin "AB21") (pinfunction "MEM_DQ[86]_AB21") (pintype "bidirectional"))
    )
    (net (code "91") (name "/DQ87") (class "Default")
      (node (ref "R131") (pin "2") (pinfunction "2_2") (pintype "passive"))
      (node (ref "R160") (pin "2") (pinfunction "2_2") (pintype "passive"))
      (node (ref "U1") (pin "AD22") (pinfunction "MEM_DQ[87]_AD22") (pintype "bidirectional"))
    )
    (net (code "92") (name "/DQ88") (class "Default")
      (node (ref "R133") (pin "2") (pinfunction "2_2") (pintype "passive"))
      (node (ref "R161") (pin "2") (pinfunction "2_2") (pintype "passive"))
      (node (ref "U1") (pin "AA21") (pinfunction "MEM_DQ[88]_AA21") (pintype "bidirectional"))
    )
    (net (code "93") (name "/DQ89") (class "Default")
      (node (ref "R135") (pin "2") (pinfunction "2_2") (pintype "passive"))
      (node (ref "R162") (pin "2") (pinfunction "2_2") (pintype "passive"))
      (node (ref "U1") (pin "AC24") (pinfunction "MEM_DQ[89]_AC24") (pintype "bidirectional"))
    )
    (net (code "94") (name "/DQ90") (class "Default")
      (node (ref "R137") (pin "2") (pinfunction "2_2") (pintype "passive"))
      (node (ref "R163") (pin "2") (pinfunction "2_2") (pintype "passive"))
      (node (ref "U1") (pin "AB23") (pinfunction "MEM_DQ[90]_AB23") (pintype "bidirectional"))
    )
    (net (code "95") (name "/DQ91") (class "Default")
      (node (ref "R139") (pin "2") (pinfunction "2_2") (pintype "passive"))
      (node (ref "R164") (pin "2") (pinfunction "2_2") (pintype "passive"))
      (node (ref "U1") (pin "AC23") (pinfunction "MEM_DQ[91]_AC23") (pintype "bidirectional"))
    )
    (net (code "96") (name "/DQ92") (class "Default")
      (node (ref "R141") (pin "2") (pinfunction "2_2") (pintype "passive"))
      (node (ref "R165") (pin "2") (pinfunction "2_2") (pintype "passive"))
      (node (ref "U1") (pin "AA22") (pinfunction "MEM_DQ[92]_AA22") (pintype "bidirectional"))
    )
    (net (code "97") (name "/DQ93") (class "Default")
      (node (ref "R143") (pin "2") (pinfunction "2_2") (pintype "passive"))
      (node (ref "R166") (pin "2") (pinfunction "2_2") (pintype "passive"))
      (node (ref "U1") (pin "AB25") (pinfunction "MEM_DQ[93]_AB25") (pintype "bidirectional"))
    )
    (net (code "98") (name "/DQ94") (class "Default")
      (node (ref "R145") (pin "2") (pinfunction "2_2") (pintype "passive"))
      (node (ref "R167") (pin "2") (pinfunction "2_2") (pintype "passive"))
      (node (ref "U1") (pin "AA23") (pinfunction "MEM_DQ[94]_AA23") (pintype "bidirectional"))
    )
    (net (code "99") (name "/DQ95") (class "Default")
      (node (ref "R147") (pin "2") (pinfunction "2_2") (pintype "passive"))
      (node (ref "R168") (pin "2") (pinfunction "2_2") (pintype "passive"))
      (node (ref "U1") (pin "AB24") (pinfunction "MEM_DQ[95]_AB24") (pintype "bidirectional"))
    )
    (net (code "100") (name "/DQM0") (class "Default")
      (node (ref "R313") (pin "2") (pinfunction "2_2") (pintype "passive"))
      (node (ref "U1") (pin "U4") (pinfunction "MEM_DQM[0]_U4") (pintype "output"))
    )
    (net (code "101") (name "/DQM1") (class "Default")
      (node (ref "R315") (pin "2") (pinfunction "2_2") (pintype "passive"))
      (node (ref "U1") (pin "U2") (pinfunction "MEM_DQM[1]_U2") (pintype "output"))
    )
    (net (code "102") (name "/DQM2") (class "Default")
      (node (ref "R317") (pin "2") (pinfunction "2_2") (pintype "passive"))
      (node (ref "U1") (pin "AA3") (pinfunction "MEM_DQM[2]_AA3") (pintype "output"))
    )
    (net (code "103") (name "/DQM3") (class "Default")
      (node (ref "R319") (pin "2") (pinfunction "2_2") (pintype "passive"))
      (node (ref "U1") (pin "AB1") (pinfunction "MEM_DQM[3]_AB1") (pintype "output"))
    )
    (net (code "104") (name "/DQM4") (class "Default")
      (node (ref "R169") (pin "2") (pinfunction "2_2") (pintype "passive"))
      (node (ref "R88") (pin "2") (pinfunction "2_2") (pintype "passive"))
      (node (ref "U1") (pin "AB6") (pinfunction "MEM_DQM[4]_AB6") (pintype "output"))
    )
    (net (code "105") (name "/DQM5") (class "Default")
      (node (ref "R170") (pin "2") (pinfunction "2_2") (pintype "passive"))
      (node (ref "R90") (pin "2") (pinfunction "2_2") (pintype "passive"))
      (node (ref "U1") (pin "AE5") (pinfunction "MEM_DQM[5]_AE5") (pintype "output"))
    )
    (net (code "106") (name "/DQM6") (class "Default")
      (node (ref "R171") (pin "2") (pinfunction "2_2") (pintype "passive"))
      (node (ref "R92") (pin "2") (pinfunction "2_2") (pintype "passive"))
      (node (ref "U1") (pin "AD15") (pinfunction "MEM_DQM[6]_AD15") (pintype "output"))
    )
    (net (code "107") (name "/DQM7") (class "Default")
      (node (ref "R172") (pin "2") (pinfunction "2_2") (pintype "passive"))
      (node (ref "R94") (pin "2") (pinfunction "2_2") (pintype "passive"))
      (node (ref "U1") (pin "AA16") (pinfunction "MEM_DQM[7]_AA16") (pintype "output"))
    )
    (net (code "108") (name "/DQM8") (class "Default")
      (node (ref "R325") (pin "2") (pinfunction "2_2") (pintype "passive"))
      (node (ref "U1") (pin "AD19") (pinfunction "MEM_DQM[8]_AD19") (pintype "output"))
    )
    (net (code "109") (name "/DQM9") (class "Default")
      (node (ref "R327") (pin "2") (pinfunction "2_2") (pintype "passive"))
      (node (ref "U1") (pin "AC19") (pinfunction "MEM_DQM[9]_AC19") (pintype "output"))
    )
    (net (code "110") (name "/DQM10") (class "Default")
      (node (ref "R173") (pin "2") (pinfunction "2_2") (pintype "passive"))
      (node (ref "R98") (pin "2") (pinfunction "2_2") (pintype "passive"))
      (node (ref "U1") (pin "AB22") (pinfunction "MEM_DQM[10]_AB22") (pintype "output"))
    )
    (net (code "111") (name "/DQM11") (class "Default")
      (node (ref "R100") (pin "2") (pinfunction "2_2") (pintype "passive"))
      (node (ref "R174") (pin "2") (pinfunction "2_2") (pintype "passive"))
      (node (ref "U1") (pin "AC25") (pinfunction "MEM_DQM[11]_AC25") (pintype "output"))
    )
    (net (code "112") (name "/MEM_BA0") (class "Default")
      (node (ref "U1") (pin "AB12") (pinfunction "MEM_BA[0]_AB12") (pintype "output"))
    )
    (net (code "113") (name "/MEM_BA1") (class "Default")
      (node (ref "U1") (pin "AE12") (pinfunction "MEM_BA[1]_AE12") (pintype "output"))
    )
    (net (code "115") (name "/MEM_CAS") (class "Default")
      (node (ref "U1") (pin "AA12") (pinfunction "MEM_CASN_AA12") (pintype "output"))
    )
    (net (code "116") (name "/MEM_CKE") (class "Default")
      (node (ref "U1") (pin "AE13") (pinfunction "MEM_CKE[0]_AE13") (pintype "output"))
    )
    (net (code "117") (name "/MEM_CLK_N") (class "Default")
      (node (ref "U1") (pin "AA25") (pinfunction "MEM_CLK_OUT_DIFF_N_AA25") (pintype "output"))
    )
    (net (code "118") (name "/MEM_CLK_OUT") (class "Default")
      (node (ref "U1") (pin "Y20") (pinfunction "MEM_CLK_OUT_Y20") (pintype "output"))
    )
    (net (code "119") (name "/MEM_CLK_P") (class "Default")
      (node (ref "U1") (pin "AA24") (pinfunction "MEM_CLK_OUT_DIFF_P_AA24") (pintype "output"))
    )
    (net (code "120") (name "/MEM_CS") (class "Default")
      (node (ref "U1") (pin "AD8") (pinfunction "MEM_SN[0]_AD8") (pintype "output"))
    )
    (net (code "121") (name "/MEM_DQ0") (class "Default")
      (node (ref "R30") (pin "2") (pinfunction "2_2") (pintype "passive"))
    )
    (net (code "122") (name "/MEM_DQ1") (class "Default")
      (node (ref "R295") (pin "2") (pinfunction "2_2") (pintype "passive"))
    )
    (net (code "123") (name "/MEM_DQ2") (class "Default")
      (node (ref "R296") (pin "2") (pinfunction "2_2") (pintype "passive"))
    )
    (net (code "124") (name "/MEM_DQ3") (class "Default")
      (node (ref "R297") (pin "2") (pinfunction "2_2") (pintype "passive"))
    )
    (net (code "125") (name "/MEM_DQ4") (class "Default")
      (node (ref "R298") (pin "2") (pinfunction "2_2") (pintype "passive"))
    )
    (net (code "126") (name "/MEM_DQ5") (class "Default")
      (node (ref "R299") (pin "2") (pinfunction "2_2") (pintype "passive"))
    )
    (net (code "127") (name "/MEM_DQ6") (class "Default")
      (node (ref "R300") (pin "2") (pinfunction "2_2") (pintype "passive"))
    )
    (net (code "128") (name "/MEM_DQ7") (class "Default")
      (node (ref "R301") (pin "2") (pinfunction "2_2") (pintype "passive"))
    )
    (net (code "129") (name "/MEM_DQ8") (class "Default")
      (node (ref "R302") (pin "2") (pinfunction "2_2") (pintype "passive"))
    )
    (net (code "130") (name "/MEM_DQ9") (class "Default")
      (node (ref "R303") (pin "2") (pinfunction "2_2") (pintype "passive"))
    )
    (net (code "131") (name "/MEM_DQ10") (class "Default")
      (node (ref "R304") (pin "2") (pinfunction "2_2") (pintype "passive"))
    )
    (net (code "132") (name "/MEM_DQ11") (class "Default")
      (node (ref "R305") (pin "2") (pinfunction "2_2") (pintype "passive"))
    )
    (net (code "133") (name "/MEM_DQ12") (class "Default")
      (node (ref "R306") (pin "2") (pinfunction "2_2") (pintype "passive"))
    )
    (net (code "134") (name "/MEM_DQ13") (class "Default")
      (node (ref "R307") (pin "2") (pinfunction "2_2") (pintype "passive"))
    )
    (net (code "135") (name "/MEM_DQ14") (class "Default")
      (node (ref "R308") (pin "2") (pinfunction "2_2") (pintype "passive"))
    )
    (net (code "136") (name "/MEM_DQ15") (class "Default")
      (node (ref "R309") (pin "2") (pinfunction "2_2") (pintype "passive"))
    )
    (net (code "137") (name "/MEM_DQ16") (class "Default")
      (node (ref "R310") (pin "2") (pinfunction "2_2") (pintype "passive"))
    )
    (net (code "138") (name "/MEM_DQ17") (class "Default")
      (node (ref "R311") (pin "2") (pinfunction "2_2") (pintype "passive"))
    )
    (net (code "139") (name "/MEM_DQ18") (class "Default")
      (node (ref "R312") (pin "2") (pinfunction "2_2") (pintype "passive"))
    )
    (net (code "140") (name "/MEM_DQ19") (class "Default")
      (node (ref "R314") (pin "2") (pinfunction "2_2") (pintype "passive"))
    )
    (net (code "141") (name "/MEM_DQ20") (class "Default")
      (node (ref "R316") (pin "2") (pinfunction "2_2") (pintype "passive"))
    )
    (net (code "142") (name "/MEM_DQ21") (class "Default")
      (node (ref "R318") (pin "2") (pinfunction "2_2") (pintype "passive"))
    )
    (net (code "143") (name "/MEM_DQ22") (class "Default")
      (node (ref "R320") (pin "2") (pinfunction "2_2") (pintype "passive"))
    )
    (net (code "144") (name "/MEM_DQ23") (class "Default")
      (node (ref "R321") (pin "2") (pinfunction "2_2") (pintype "passive"))
    )
    (net (code "145") (name "/MEM_DQ24") (class "Default")
      (node (ref "R322") (pin "2") (pinfunction "2_2") (pintype "passive"))
    )
    (net (code "146") (name "/MEM_DQ25") (class "Default")
      (node (ref "R323") (pin "2") (pinfunction "2_2") (pintype "passive"))
    )
    (net (code "147") (name "/MEM_DQ26") (class "Default")
      (node (ref "R324") (pin "2") (pinfunction "2_2") (pintype "passive"))
    )
    (net (code "148") (name "/MEM_DQ27") (class "Default")
      (node (ref "R326") (pin "2") (pinfunction "2_2") (pintype "passive"))
    )
    (net (code "149") (name "/MEM_DQ28") (class "Default")
      (node (ref "R328") (pin "2") (pinfunction "2_2") (pintype "passive"))
    )
    (net (code "150") (name "/MEM_DQ29") (class "Default")
      (node (ref "R329") (pin "2") (pinfunction "2_2") (pintype "passive"))
    )
    (net (code "151") (name "/MEM_DQ30") (class "Default")
      (node (ref "R330") (pin "2") (pinfunction "2_2") (pintype "passive"))
    )
    (net (code "152") (name "/MEM_DQ31") (class "Default")
      (node (ref "R331") (pin "2") (pinfunction "2_2") (pintype "passive"))
    )
    (net (code "153") (name "/MEM_DQ32") (class "Default")
      (node (ref "R101") (pin "2") (pinfunction "2_2") (pintype "passive"))
    )
    (net (code "154") (name "/MEM_DQ33") (class "Default")
      (node (ref "R102") (pin "2") (pinfunction "2_2") (pintype "passive"))
    )
    (net (code "155") (name "/MEM_DQ34") (class "Default")
      (node (ref "R103") (pin "2") (pinfunction "2_2") (pintype "passive"))
    )
    (net (code "156") (name "/MEM_DQ35") (class "Default")
      (node (ref "R104") (pin "2") (pinfunction "2_2") (pintype "passive"))
    )
    (net (code "157") (name "/MEM_DQ36") (class "Default")
      (node (ref "R105") (pin "2") (pinfunction "2_2") (pintype "passive"))
    )
    (net (code "158") (name "/MEM_DQ37") (class "Default")
      (node (ref "R106") (pin "2") (pinfunction "2_2") (pintype "passive"))
    )
    (net (code "159") (name "/MEM_DQ38") (class "Default")
      (node (ref "R107") (pin "2") (pinfunction "2_2") (pintype "passive"))
    )
    (net (code "160") (name "/MEM_DQ39") (class "Default")
      (node (ref "R108") (pin "2") (pinfunction "2_2") (pintype "passive"))
    )
    (net (code "161") (name "/MEM_DQ40") (class "Default")
      (node (ref "R109") (pin "2") (pinfunction "2_2") (pintype "passive"))
    )
    (net (code "162") (name "/MEM_DQ41") (class "Default")
      (node (ref "R110") (pin "2") (pinfunction "2_2") (pintype "passive"))
    )
    (net (code "163") (name "/MEM_DQ42") (class "Default")
      (node (ref "R111") (pin "2") (pinfunction "2_2") (pintype "passive"))
    )
    (net (code "164") (name "/MEM_DQ43") (class "Default")
      (node (ref "R112") (pin "2") (pinfunction "2_2") (pintype "passive"))
    )
    (net (code "165") (name "/MEM_DQ44") (class "Default")
      (node (ref "R113") (pin "2") (pinfunction "2_2") (pintype "passive"))
    )
    (net (code "166") (name "/MEM_DQ45") (class "Default")
      (node (ref "R114") (pin "2") (pinfunction "2_2") (pintype "passive"))
    )
    (net (code "167") (name "/MEM_DQ46") (class "Default")
      (node (ref "R115") (pin "2") (pinfunction "2_2") (pintype "passive"))
    )
    (net (code "168") (name "/MEM_DQ47") (class "Default")
      (node (ref "R116") (pin "2") (pinfunction "2_2") (pintype "passive"))
    )
    (net (code "169") (name "/MEM_DQ48") (class "Default")
      (node (ref "R118") (pin "2") (pinfunction "2_2") (pintype "passive"))
    )
    (net (code "170") (name "/MEM_DQ49") (class "Default")
      (node (ref "R120") (pin "2") (pinfunction "2_2") (pintype "passive"))
    )
    (net (code "171") (name "/MEM_DQ50") (class "Default")
      (node (ref "R122") (pin "2") (pinfunction "2_2") (pintype "passive"))
    )
    (net (code "172") (name "/MEM_DQ51") (class "Default")
      (node (ref "R124") (pin "2") (pinfunction "2_2") (pintype "passive"))
    )
    (net (code "173") (name "/MEM_DQ52") (class "Default")
      (node (ref "R126") (pin "2") (pinfunction "2_2") (pintype "passive"))
    )
    (net (code "174") (name "/MEM_DQ53") (class "Default")
      (node (ref "R128") (pin "2") (pinfunction "2_2") (pintype "passive"))
    )
    (net (code "175") (name "/MEM_DQ54") (class "Default")
      (node (ref "R130") (pin "2") (pinfunction "2_2") (pintype "passive"))
    )
    (net (code "176") (name "/MEM_DQ55") (class "Default")
      (node (ref "R132") (pin "2") (pinfunction "2_2") (pintype "passive"))
    )
    (net (code "177") (name "/MEM_DQ56") (class "Default")
      (node (ref "R134") (pin "2") (pinfunction "2_2") (pintype "passive"))
    )
    (net (code "178") (name "/MEM_DQ57") (class "Default")
      (node (ref "R136") (pin "2") (pinfunction "2_2") (pintype "passive"))
    )
    (net (code "179") (name "/MEM_DQ58") (class "Default")
      (node (ref "R138") (pin "2") (pinfunction "2_2") (pintype "passive"))
    )
    (net (code "180") (name "/MEM_DQ59") (class "Default")
      (node (ref "R140") (pin "2") (pinfunction "2_2") (pintype "passive"))
    )
    (net (code "181") (name "/MEM_DQ60") (class "Default")
      (node (ref "R142") (pin "2") (pinfunction "2_2") (pintype "passive"))
    )
    (net (code "182") (name "/MEM_DQ61") (class "Default")
      (node (ref "R144") (pin "2") (pinfunction "2_2") (pintype "passive"))
    )
    (net (code "183") (name "/MEM_DQ62") (class "Default")
      (node (ref "R146") (pin "2") (pinfunction "2_2") (pintype "passive"))
    )
    (net (code "184") (name "/MEM_DQ63") (class "Default")
      (node (ref "R148") (pin "2") (pinfunction "2_2") (pintype "passive"))
    )
    (net (code "185") (name "/MEM_DQ64") (class "Default")
      (node (ref "R332") (pin "1") (pinfunction "1_1") (pintype "passive"))
    )
    (net (code "186") (name "/MEM_DQ65") (class "Default")
      (node (ref "R333") (pin "1") (pinfunction "1_1") (pintype "passive"))
    )
    (net (code "187") (name "/MEM_DQ66") (class "Default")
      (node (ref "R334") (pin "1") (pinfunction "1_1") (pintype "passive"))
    )
    (net (code "188") (name "/MEM_DQ67") (class "Default")
      (node (ref "R335") (pin "1") (pinfunction "1_1") (pintype "passive"))
    )
    (net (code "189") (name "/MEM_DQ68") (class "Default")
      (node (ref "R336") (pin "1") (pinfunction "1_1") (pintype "passive"))
    )
    (net (code "190") (name "/MEM_DQ69") (class "Default")
      (node (ref "R337") (pin "1") (pinfunction "1_1") (pintype "passive"))
    )
    (net (code "191") (name "/MEM_DQ70") (class "Default")
      (node (ref "R338") (pin "1") (pinfunction "1_1") (pintype "passive"))
    )
    (net (code "192") (name "/MEM_DQ71") (class "Default")
      (node (ref "R339") (pin "1") (pinfunction "1_1") (pintype "passive"))
    )
    (net (code "193") (name "/MEM_DQ72") (class "Default")
      (node (ref "R340") (pin "1") (pinfunction "1_1") (pintype "passive"))
    )
    (net (code "194") (name "/MEM_DQ73") (class "Default")
      (node (ref "R341") (pin "1") (pinfunction "1_1") (pintype "passive"))
    )
    (net (code "195") (name "/MEM_DQ74") (class "Default")
      (node (ref "R342") (pin "1") (pinfunction "1_1") (pintype "passive"))
    )
    (net (code "196") (name "/MEM_DQ75") (class "Default")
      (node (ref "R343") (pin "1") (pinfunction "1_1") (pintype "passive"))
    )
    (net (code "197") (name "/MEM_DQ76") (class "Default")
      (node (ref "R344") (pin "1") (pinfunction "1_1") (pintype "passive"))
    )
    (net (code "198") (name "/MEM_DQ77") (class "Default")
      (node (ref "R345") (pin "1") (pinfunction "1_1") (pintype "passive"))
    )
    (net (code "199") (name "/MEM_DQ78") (class "Default")
      (node (ref "R346") (pin "1") (pinfunction "1_1") (pintype "passive"))
    )
    (net (code "200") (name "/MEM_DQ79") (class "Default")
      (node (ref "R347") (pin "1") (pinfunction "1_1") (pintype "passive"))
    )
    (net (code "201") (name "/MEM_DQ80") (class "Default")
      (node (ref "R149") (pin "1") (pinfunction "1_1") (pintype "passive"))
    )
    (net (code "202") (name "/MEM_DQ81") (class "Default")
      (node (ref "R154") (pin "1") (pinfunction "1_1") (pintype "passive"))
    )
    (net (code "203") (name "/MEM_DQ82") (class "Default")
      (node (ref "R155") (pin "1") (pinfunction "1_1") (pintype "passive"))
    )
    (net (code "204") (name "/MEM_DQ83") (class "Default")
      (node (ref "R156") (pin "1") (pinfunction "1_1") (pintype "passive"))
    )
    (net (code "205") (name "/MEM_DQ84") (class "Default")
      (node (ref "R157") (pin "1") (pinfunction "1_1") (pintype "passive"))
    )
    (net (code "206") (name "/MEM_DQ85") (class "Default")
      (node (ref "R158") (pin "1") (pinfunction "1_1") (pintype "passive"))
    )
    (net (code "207") (name "/MEM_DQ86") (class "Default")
      (node (ref "R159") (pin "1") (pinfunction "1_1") (pintype "passive"))
    )
    (net (code "208") (name "/MEM_DQ87") (class "Default")
      (node (ref "R160") (pin "1") (pinfunction "1_1") (pintype "passive"))
    )
    (net (code "209") (name "/MEM_DQ88") (class "Default")
      (node (ref "R161") (pin "1") (pinfunction "1_1") (pintype "passive"))
    )
    (net (code "210") (name "/MEM_DQ89") (class "Default")
      (node (ref "R162") (pin "1") (pinfunction "1_1") (pintype "passive"))
    )
    (net (code "211") (name "/MEM_DQ90") (class "Default")
      (node (ref "R163") (pin "1") (pinfunction "1_1") (pintype "passive"))
    )
    (net (code "212") (name "/MEM_DQ91") (class "Default")
      (node (ref "R164") (pin "1") (pinfunction "1_1") (pintype "passive"))
    )
    (net (code "213") (name "/MEM_DQ92") (class "Default")
      (node (ref "R165") (pin "1") (pinfunction "1_1") (pintype "passive"))
    )
    (net (code "214") (name "/MEM_DQ93") (class "Default")
      (node (ref "R166") (pin "1") (pinfunction "1_1") (pintype "passive"))
    )
    (net (code "215") (name "/MEM_DQ94") (class "Default")
      (node (ref "R167") (pin "1") (pinfunction "1_1") (pintype "passive"))
    )
    (net (code "216") (name "/MEM_DQ95") (class "Default")
      (node (ref "R168") (pin "1") (pinfunction "1_1") (pintype "passive"))
    )
    (net (code "217") (name "/MEM_DQM0") (class "Default")
      (node (ref "R313") (pin "1") (pinfunction "1_1") (pintype "passive"))
    )
    (net (code "218") (name "/MEM_DQM1") (class "Default")
      (node (ref "R315") (pin "1") (pinfunction "1_1") (pintype "passive"))
    )
    (net (code "219") (name "/MEM_DQM2") (class "Default")
      (node (ref "R317") (pin "1") (pinfunction "1_1") (pintype "passive"))
    )
    (net (code "220") (name "/MEM_DQM3") (class "Default")
      (node (ref "R319") (pin "1") (pinfunction "1_1") (pintype "passive"))
    )
    (net (code "221") (name "/MEM_DQM4") (class "Default")
      (node (ref "R169") (pin "1") (pinfunction "1_1") (pintype "passive"))
    )
    (net (code "222") (name "/MEM_DQM5") (class "Default")
      (node (ref "R170") (pin "1") (pinfunction "1_1") (pintype "passive"))
    )
    (net (code "223") (name "/MEM_DQM6") (class "Default")
      (node (ref "R171") (pin "1") (pinfunction "1_1") (pintype "passive"))
    )
    (net (code "224") (name "/MEM_DQM7") (class "Default")
      (node (ref "R172") (pin "1") (pinfunction "1_1") (pintype "passive"))
    )
    (net (code "225") (name "/MEM_DQM8") (class "Default")
      (node (ref "R325") (pin "1") (pinfunction "1_1") (pintype "passive"))
    )
    (net (code "226") (name "/MEM_DQM9") (class "Default")
      (node (ref "R327") (pin "1") (pinfunction "1_1") (pintype "passive"))
    )
    (net (code "227") (name "/MEM_DQM10") (class "Default")
      (node (ref "R173") (pin "1") (pinfunction "1_1") (pintype "passive"))
    )
    (net (code "228") (name "/MEM_DQM11") (class "Default")
      (node (ref "R174") (pin "1") (pinfunction "1_1") (pintype "passive"))
    )
    (net (code "231") (name "/MEM_RAS") (class "Default")
      (node (ref "U1") (pin "AD13") (pinfunction "MEM_RASN_AD13") (pintype "output"))
    )
    (net (code "232") (name "/MEM_WE") (class "Default")
      (node (ref "U1") (pin "AA13") (pinfunction "MEM_WEN_AA13") (pintype "output"))
    )
    (net (code "233") (name "/PCI_HOSTN") (class "Default")
      (node (ref "R98") (pin "1") (pinfunction "1_1") (pintype "passive"))
    )
    (net (code "234") (name "/PCI_INTA") (class "Default")
      (node (ref "R64") (pin "2") (pinfunction "2_2") (pintype "passive"))
    )
    (net (code "235") (name "/PCI_INTB") (class "Default")
      (node (ref "R63") (pin "2") (pinfunction "2_2") (pintype "passive"))
    )
    (net (code "236") (name "/PCI_INTC") (class "Default")
      (node (ref "R90") (pin "1") (pinfunction "1_1") (pintype "passive"))
    )
    (net (code "237") (name "/PCI_INTD") (class "Default")
      (node (ref "R88") (pin "1") (pinfunction "1_1") (pintype "passive"))
    )
    (net (code "239") (name "/PROM_A0") (class "Default")
      (node (ref "U1") (pin "B5") (pinfunction "PROMIO_ADDR[0]_B5") (pintype "output"))
    )
    (net (code "240") (name "/PROM_A1") (class "Default")
      (node (ref "U1") (pin "E6") (pinfunction "PROMIO_ADDR[1]_E6") (pintype "output"))
    )
    (net (code "241") (name "/PROM_A2") (class "Default")
      (node (ref "U1") (pin "A4") (pinfunction "PROMIO_ADDR[2]_A4") (pintype "output"))
    )
    (net (code "242") (name "/PROM_A3") (class "Default")
      (node (ref "U1") (pin "C4") (pinfunction "PROMIO_ADDR[3]_C4") (pintype "output"))
    )
    (net (code "243") (name "/PROM_A4") (class "Default")
      (node (ref "U1") (pin "B4") (pinfunction "PROMIO_ADDR[4]_B4") (pintype "output"))
    )
    (net (code "244") (name "/PROM_A5") (class "Default")
      (node (ref "U1") (pin "D4") (pinfunction "PROMIO_ADDR[5]_D4") (pintype "output"))
    )
    (net (code "245") (name "/PROM_A6") (class "Default")
      (node (ref "U1") (pin "A3") (pinfunction "PROMIO_ADDR[6]_A3") (pintype "output"))
    )
    (net (code "246") (name "/PROM_A7") (class "Default")
      (node (ref "U1") (pin "C3") (pinfunction "PROMIO_ADDR[7]_C3") (pintype "output"))
    )
    (net (code "247") (name "/PROM_A8") (class "Default")
      (node (ref "U1") (pin "B3") (pinfunction "PROMIO_ADDR[8]_B3") (pintype "output"))
    )
    (net (code "248") (name "/PROM_A9") (class "Default")
      (node (ref "U1") (pin "B2") (pinfunction "PROMIO_ADDR[9]_B2") (pintype "output"))
    )
    (net (code "249") (name "/PROM_A10") (class "Default")
      (node (ref "U1") (pin "C1") (pinfunction "PROMIO_ADDR[10]_C1") (pintype "output"))
    )
    (net (code "250") (name "/PROM_A11") (class "Default")
      (node (ref "U1") (pin "D3") (pinfunction "PROMIO_ADDR[11]_D3") (pintype "output"))
    )
    (net (code "251") (name "/PROM_A12") (class "Default")
      (node (ref "U1") (pin "C2") (pinfunction "PROMIO_ADDR[12]_C2") (pintype "output"))
    )
    (net (code "252") (name "/PROM_A13") (class "Default")
      (node (ref "U1") (pin "E5") (pinfunction "PROMIO_ADDR[13]_E5") (pintype "output"))
    )
    (net (code "253") (name "/PROM_A14") (class "Default")
      (node (ref "U1") (pin "D1") (pinfunction "PROMIO_ADDR[14]_D1") (pintype "output"))
    )
    (net (code "254") (name "/PROM_A15") (class "Default")
      (node (ref "U1") (pin "E4") (pinfunction "PROMIO_ADDR[15]_E4") (pintype "output"))
    )
    (net (code "255") (name "/PROM_A16") (class "Default")
      (node (ref "U1") (pin "D2") (pinfunction "PROMIO_ADDR[16]_D2") (pintype "output"))
    )
    (net (code "256") (name "/PROM_A17") (class "Default")
      (node (ref "U1") (pin "F5") (pinfunction "PROMIO_ADDR[17]_F5") (pintype "output"))
    )
    (net (code "257") (name "/PROM_A18") (class "Default")
      (node (ref "U1") (pin "E1") (pinfunction "PROMIO_ADDR[18]_E1") (pintype "output"))
    )
    (net (code "258") (name "/PROM_A19") (class "Default")
      (node (ref "U1") (pin "F4") (pinfunction "PROMIO_ADDR[19]_F4") (pintype "output"))
    )
    (net (code "259") (name "/PROM_A20") (class "Default")
      (node (ref "U1") (pin "E2") (pinfunction "PROMIO_ADDR[20]_E2") (pintype "output"))
    )
    (net (code "260") (name "/PROM_A21") (class "Default")
      (node (ref "U1") (pin "G5") (pinfunction "PROMIO_ADDR[21]_G5") (pintype "output"))
    )
    (net (code "261") (name "/PROM_A22") (class "Default")
      (node (ref "U1") (pin "F1") (pinfunction "PROMIO_ADDR[22]_F1") (pintype "output"))
    )
    (net (code "262") (name "/PROM_A23") (class "Default")
      (node (ref "U1") (pin "G4") (pinfunction "PROMIO_ADDR[23]_G4") (pintype "output"))
    )
    (net (code "263") (name "/PROM_A24") (class "Default")
      (node (ref "U1") (pin "F2") (pinfunction "PROMIO_ADDR[24]_F2") (pintype "output"))
    )
    (net (code "264") (name "/PROM_CEN0") (class "Default")
      (node (ref "U1") (pin "H2") (pinfunction "PROM_CEN[0]_H2") (pintype "output"))
    )
    (net (code "265") (name "/PROM_CEN1") (class "Default")
      (node (ref "U1") (pin "H1") (pinfunction "PROM_CEN[1]_H1") (pintype "output"))
    )
    (net (code "267") (name "/PROM_DATA0") (class "Default")
      (node (ref "U1") (pin "C9") (pinfunction "PROMIO_DATA[0]_C9") (pintype "bidirectional"))
    )
    (net (code "268") (name "/PROM_DATA1") (class "Default")
      (node (ref "U1") (pin "E8") (pinfunction "PROMIO_DATA[1]_E8") (pintype "bidirectional"))
    )
    (net (code "269") (name "/PROM_DATA2") (class "Default")
      (node (ref "U1") (pin "A9") (pinfunction "PROMIO_DATA[2]_A9") (pintype "bidirectional"))
    )
    (net (code "270") (name "/PROM_DATA3") (class "Default")
      (node (ref "U1") (pin "D8") (pinfunction "PROMIO_DATA[3]_D8") (pintype "bidirectional"))
    )
    (net (code "271") (name "/PROM_DATA4") (class "Default")
      (node (ref "U1") (pin "B9") (pinfunction "PROMIO_DATA[4]_B9") (pintype "bidirectional"))
    )
    (net (code "272") (name "/PROM_DATA5") (class "Default")
      (node (ref "U1") (pin "C8") (pinfunction "PROMIO_DATA[5]_C8") (pintype "bidirectional"))
    )
    (net (code "273") (name "/PROM_DATA6") (class "Default")
      (node (ref "U1") (pin "A8") (pinfunction "PROMIO_DATA[6]_A8") (pintype "bidirectional"))
    )
    (net (code "274") (name "/PROM_DATA7") (class "Default")
      (node (ref "U1") (pin "E7") (pinfunction "PROMIO_DATA[7]_E7") (pintype "bidirectional"))
    )
    (net (code "275") (name "/PROM_DATA8") (class "Default")
      (node (ref "U1") (pin "B8") (pinfunction "PROMIO_DATA[8]_B8") (pintype "bidirectional"))
    )
    (net (code "276") (name "/PROM_DATA9") (class "Default")
      (node (ref "U1") (pin "C7") (pinfunction "PROMIO_DATA[9]_C7") (pintype "bidirectional"))
    )
    (net (code "277") (name "/PROM_DATA10") (class "Default")
      (node (ref "U1") (pin "A7") (pinfunction "PROMIO_DATA[10]_A7") (pintype "bidirectional"))
    )
    (net (code "278") (name "/PROM_DATA11") (class "Default")
      (node (ref "U1") (pin "D7") (pinfunction "PROMIO_DATA[11]_D7") (pintype "bidirectional"))
    )
    (net (code "279") (name "/PROM_DATA12") (class "Default")
      (node (ref "U1") (pin "B7") (pinfunction "PROMIO_DATA[12]_B7") (pintype "bidirectional"))
    )
    (net (code "280") (name "/PROM_DATA13") (class "Default")
      (node (ref "U1") (pin "D6") (pinfunction "PROMIO_DATA[13]_D6") (pintype "bidirectional"))
    )
    (net (code "281") (name "/PROM_DATA14") (class "Default")
      (node (ref "U1") (pin "A6") (pinfunction "PROMIO_DATA[14]_A6") (pintype "bidirectional"))
    )
    (net (code "282") (name "/PROM_DATA15") (class "Default")
      (node (ref "U1") (pin "C6") (pinfunction "PROMIO_DATA[15]_C6") (pintype "bidirectional"))
    )
    (net (code "284") (name "/PROM_OE") (class "Default")
      (node (ref "U1") (pin "C5") (pinfunction "PROMIO_OEN_C5") (pintype "output"))
    )
    (net (code "285") (name "/PROM_READ") (class "Default")
      (node (ref "U1") (pin "B6") (pinfunction "PROMIO_READ_B6") (pintype "output"))
    )
    (net (code "286") (name "/PROM_WEN") (class "Default")
      (node (ref "U1") (pin "A5") (pinfunction "PROMIO_WEN_A5") (pintype "output"))
    )
    (net (code "288") (name "/RAM_A0") (class "Default")
      (node (ref "U1") (pin "AE8") (pinfunction "MEM_ADDR[0]_AE8") (pintype "output"))
    )
    (net (code "289") (name "/RAM_A1") (class "Default")
      (node (ref "U1") (pin "AB9") (pinfunction "MEM_ADDR[1]_AB9") (pintype "output"))
    )
    (net (code "290") (name "/RAM_A2") (class "Default")
      (node (ref "U1") (pin "AD9") (pinfunction "MEM_ADDR[2]_AD9") (pintype "output"))
    )
    (net (code "291") (name "/RAM_A3") (class "Default")
      (node (ref "U1") (pin "AB10") (pinfunction "MEM_ADDR[3]_AB10") (pintype "output"))
    )
    (net (code "292") (name "/RAM_A4") (class "Default")
      (node (ref "U1") (pin "AE9") (pinfunction "MEM_ADDR[4]_AE9") (pintype "output"))
    )
    (net (code "293") (name "/RAM_A5") (class "Default")
      (node (ref "U1") (pin "AC10") (pinfunction "MEM_ADDR[5]_AC10") (pintype "output"))
    )
    (net (code "294") (name "/RAM_A6") (class "Default")
      (node (ref "U1") (pin "AD10") (pinfunction "MEM_ADDR[6]_AD10") (pintype "output"))
    )
    (net (code "295") (name "/RAM_A7") (class "Default")
      (node (ref "U1") (pin "AA10") (pinfunction "MEM_ADDR[7]_AA10") (pintype "output"))
    )
    (net (code "296") (name "/RAM_A8") (class "Default")
      (node (ref "U1") (pin "AE10") (pinfunction "MEM_ADDR[8]_AE10") (pintype "output"))
    )
    (net (code "297") (name "/RAM_A9") (class "Default")
      (node (ref "U1") (pin "AC11") (pinfunction "MEM_ADDR[9]_AC11") (pintype "output"))
    )
    (net (code "298") (name "/RAM_A10") (class "Default")
      (node (ref "U1") (pin "AD11") (pinfunction "MEM_ADDR[10]_AD11") (pintype "output"))
    )
    (net (code "299") (name "/RAM_A11") (class "Default")
      (node (ref "U1") (pin "AB11") (pinfunction "MEM_ADDR[11]_AB11") (pintype "output"))
    )
    (net (code "300") (name "/RAM_A12") (class "Default")
      (node (ref "U1") (pin "AE11") (pinfunction "MEM_ADDR[12]_AE11") (pintype "output"))
    )
    (net (code "302") (name "/X_AD0") (class "Default")
      (node (ref "R79") (pin "2") (pinfunction "2_2") (pintype "passive"))
    )
    (net (code "303") (name "/X_AD1") (class "Default")
      (node (ref "R80") (pin "2") (pinfunction "2_2") (pintype "passive"))
    )
    (net (code "304") (name "/X_AD2") (class "Default")
      (node (ref "R81") (pin "2") (pinfunction "2_2") (pintype "passive"))
    )
    (net (code "305") (name "/X_AD3") (class "Default")
      (node (ref "R82") (pin "2") (pinfunction "2_2") (pintype "passive"))
    )
    (net (code "306") (name "/X_AD4") (class "Default")
      (node (ref "R83") (pin "2") (pinfunction "2_2") (pintype "passive"))
    )
    (net (code "307") (name "/X_AD5") (class "Default")
      (node (ref "R84") (pin "2") (pinfunction "2_2") (pintype "passive"))
    )
    (net (code "308") (name "/X_AD6") (class "Default")
      (node (ref "R85") (pin "2") (pinfunction "2_2") (pintype "passive"))
    )
    (net (code "309") (name "/X_AD7") (class "Default")
      (node (ref "R86") (pin "2") (pinfunction "2_2") (pintype "passive"))
    )
    (net (code "310") (name "/X_AD8") (class "Default")
      (node (ref "R87") (pin "2") (pinfunction "2_2") (pintype "passive"))
    )
    (net (code "311") (name "/X_AD9") (class "Default")
      (node (ref "R89") (pin "2") (pinfunction "2_2") (pintype "passive"))
    )
    (net (code "312") (name "/X_AD10") (class "Default")
      (node (ref "R91") (pin "2") (pinfunction "2_2") (pintype "passive"))
    )
    (net (code "313") (name "/X_AD11") (class "Default")
      (node (ref "R93") (pin "2") (pinfunction "2_2") (pintype "passive"))
    )
    (net (code "314") (name "/X_AD12") (class "Default")
      (node (ref "R95") (pin "2") (pinfunction "2_2") (pintype "passive"))
    )
    (net (code "315") (name "/X_AD13") (class "Default")
      (node (ref "R96") (pin "2") (pinfunction "2_2") (pintype "passive"))
    )
    (net (code "316") (name "/X_AD14") (class "Default")
      (node (ref "R97") (pin "2") (pinfunction "2_2") (pintype "passive"))
    )
    (net (code "317") (name "/X_AD15") (class "Default")
      (node (ref "R99") (pin "2") (pinfunction "2_2") (pintype "passive"))
    )
    (net (code "318") (name "/X_AD16") (class "Default")
      (node (ref "R117") (pin "1") (pinfunction "1_1") (pintype "passive"))
    )
    (net (code "319") (name "/X_AD17") (class "Default")
      (node (ref "R119") (pin "1") (pinfunction "1_1") (pintype "passive"))
    )
    (net (code "320") (name "/X_AD18") (class "Default")
      (node (ref "R121") (pin "1") (pinfunction "1_1") (pintype "passive"))
    )
    (net (code "321") (name "/X_AD19") (class "Default")
      (node (ref "R123") (pin "1") (pinfunction "1_1") (pintype "passive"))
    )
    (net (code "322") (name "/X_AD20") (class "Default")
      (node (ref "R125") (pin "1") (pinfunction "1_1") (pintype "passive"))
    )
    (net (code "323") (name "/X_AD21") (class "Default")
      (node (ref "R127") (pin "1") (pinfunction "1_1") (pintype "passive"))
    )
    (net (code "324") (name "/X_AD22") (class "Default")
      (node (ref "R129") (pin "1") (pinfunction "1_1") (pintype "passive"))
    )
    (net (code "325") (name "/X_AD23") (class "Default")
      (node (ref "R131") (pin "1") (pinfunction "1_1") (pintype "passive"))
    )
    (net (code "326") (name "/X_AD24") (class "Default")
      (node (ref "R133") (pin "1") (pinfunction "1_1") (pintype "passive"))
    )
    (net (code "327") (name "/X_AD25") (class "Default")
      (node (ref "R135") (pin "1") (pinfunction "1_1") (pintype "passive"))
    )
    (net (code "328") (name "/X_AD26") (class "Default")
      (node (ref "R137") (pin "1") (pinfunction "1_1") (pintype "passive"))
    )
    (net (code "329") (name "/X_AD27") (class "Default")
      (node (ref "R139") (pin "1") (pinfunction "1_1") (pintype "passive"))
    )
    (net (code "330") (name "/X_AD28") (class "Default")
      (node (ref "R141") (pin "1") (pinfunction "1_1") (pintype "passive"))
    )
    (net (code "331") (name "/X_AD29") (class "Default")
      (node (ref "R143") (pin "1") (pinfunction "1_1") (pintype "passive"))
    )
    (net (code "332") (name "/X_AD30") (class "Default")
      (node (ref "R145") (pin "1") (pinfunction "1_1") (pintype "passive"))
    )
    (net (code "333") (name "/X_AD31") (class "Default")
      (node (ref "R147") (pin "1") (pinfunction "1_1") (pintype "passive"))
    )
    (net (code "334") (name "/X_CBE0") (class "Default")
      (node (ref "R75") (pin "2") (pinfunction "2_2") (pintype "passive"))
    )
    (net (code "335") (name "/X_CBE1") (class "Default")
      (node (ref "R76") (pin "2") (pinfunction "2_2") (pintype "passive"))
    )
    (net (code "336") (name "/X_CBE2") (class "Default")
      (node (ref "R77") (pin "2") (pinfunction "2_2") (pintype "passive"))
    )
    (net (code "337") (name "/X_CBE3") (class "Default")
      (node (ref "R78") (pin "2") (pinfunction "2_2") (pintype "passive"))
    )
    (net (code "339") (name "/X_CLK") (class "Default")
      (node (ref "R92") (pin "1") (pinfunction "1_1") (pintype "passive"))
    )
    (net (code "340") (name "/X_DEVSEL") (class "Default")
      (node (ref "R66") (pin "2") (pinfunction "2_2") (pintype "passive"))
    )
    (net (code "341") (name "/X_FRAME") (class "Default")
      (node (ref "R74") (pin "2") (pinfunction "2_2") (pintype "passive"))
    )
    (net (code "342") (name "/X_GNT") (class "Default")
      (node (ref "R72") (pin "2") (pinfunction "2_2") (pintype "passive"))
    )
    (net (code "343") (name "/X_IDSEL") (class "Default")
      (node (ref "R94") (pin "1") (pinfunction "1_1") (pintype "passive"))
    )
    (net (code "344") (name "/X_IRDY") (class "Default")
      (node (ref "R71") (pin "2") (pinfunction "2_2") (pintype "passive"))
    )
    (net (code "345") (name "/X_M66EN") (class "Default")
      (node (ref "R100") (pin "1") (pinfunction "1_1") (pintype "passive"))
    )
    (net (code "346") (name "/X_PAR") (class "Default")
      (node (ref "R69") (pin "2") (pinfunction "2_2") (pintype "passive"))
    )
    (net (code "347") (name "/X_PERR") (class "Default")
      (node (ref "R68") (pin "2") (pinfunction "2_2") (pintype "passive"))
    )
    (net (code "348") (name "/X_REQ") (class "Default")
      (node (ref "R73") (pin "2") (pinfunction "2_2") (pintype "passive"))
    )
    (net (code "349") (name "/X_SERR") (class "Default")
      (node (ref "R67") (pin "2") (pinfunction "2_2") (pintype "passive"))
    )
    (net (code "350") (name "/X_STOP") (class "Default")
      (node (ref "R65") (pin "2") (pinfunction "2_2") (pintype "passive"))
    )
    (net (code "351") (name "/X_TRDY") (class "Default")
      (node (ref "R70") (pin "2") (pinfunction "2_2") (pintype "passive"))
    )
    (net (code "355") (name "Net-(U1E-IO_SN)") (class "Default")
      (node (ref "TP17") (pin "1") (pinfunction "1_1") (pintype "bidirectional"))
      (node (ref "U1") (pin "G2") (pinfunction "IO_SN_G2") (pintype "output"))
    )
    (net (code "356") (name "Net-(U1E-PROMIO_BRDYN)") (class "Default")
      (node (ref "TP16") (pin "1") (pinfunction "1_1") (pintype "bidirectional"))
      (node (ref "U1") (pin "D5") (pinfunction "PROMIO_BRDYN_D5") (pintype "input"))
    )
    (net (code "357") (name "unconnected-(U1E-PROMIO_ADDR[25]-PadH5)") (class "Default")
      (node (ref "U1") (pin "H5") (pinfunction "PROMIO_ADDR[25]_H5") (pintype "output"))
    )
    (net (code "358") (name "unconnected-(U1E-PROMIO_ADDR[26]-PadG1)") (class "Default")
      (node (ref "U1") (pin "G1") (pinfunction "PROMIO_ADDR[26]_G1") (pintype "output"))
    )
    (net (code "359") (name "unconnected-(U1E-PROMIO_ADDR[27]-PadH4)") (class "Default")
      (node (ref "U1") (pin "H4") (pinfunction "PROMIO_ADDR[27]_H4") (pintype "output"))
    )
    (net (code "360") (name "unconnected-(U1F-MEM_ADDR[13]-PadAA11)") (class "Default")
      (node (ref "U1") (pin "AA11") (pinfunction "MEM_ADDR[13]_AA11") (pintype "output"))
    )
    (net (code "361") (name "unconnected-(U1F-MEM_ADDR[14]-PadAD12)") (class "Default")
      (node (ref "U1") (pin "AD12") (pinfunction "MEM_ADDR[14]_AD12") (pintype "output"))
    )
    (net (code "362") (name "unconnected-(U1F-MEM_CKE[1]-PadAB13)") (class "Default")
      (node (ref "U1") (pin "AB13") (pinfunction "MEM_CKE[1]_AB13") (pintype "output"))
    )
    (net (code "363") (name "unconnected-(U1F-MEM_CLK_IN-PadAB8)") (class "Default")
      (node (ref "U1") (pin "AB8") (pinfunction "MEM_CLK_IN_AB8") (pintype "input+no_connect"))
    )
    (net (code "364") (name "unconnected-(U1F-MEM_SN[1]-PadAA9)") (class "Default")
      (node (ref "U1") (pin "AA9") (pinfunction "MEM_SN[1]_AA9") (pintype "output"))
    )
  )
)
